# mk312_smt_main_V2b.net
KiCad netlist of a schematic drawn in EAGLE
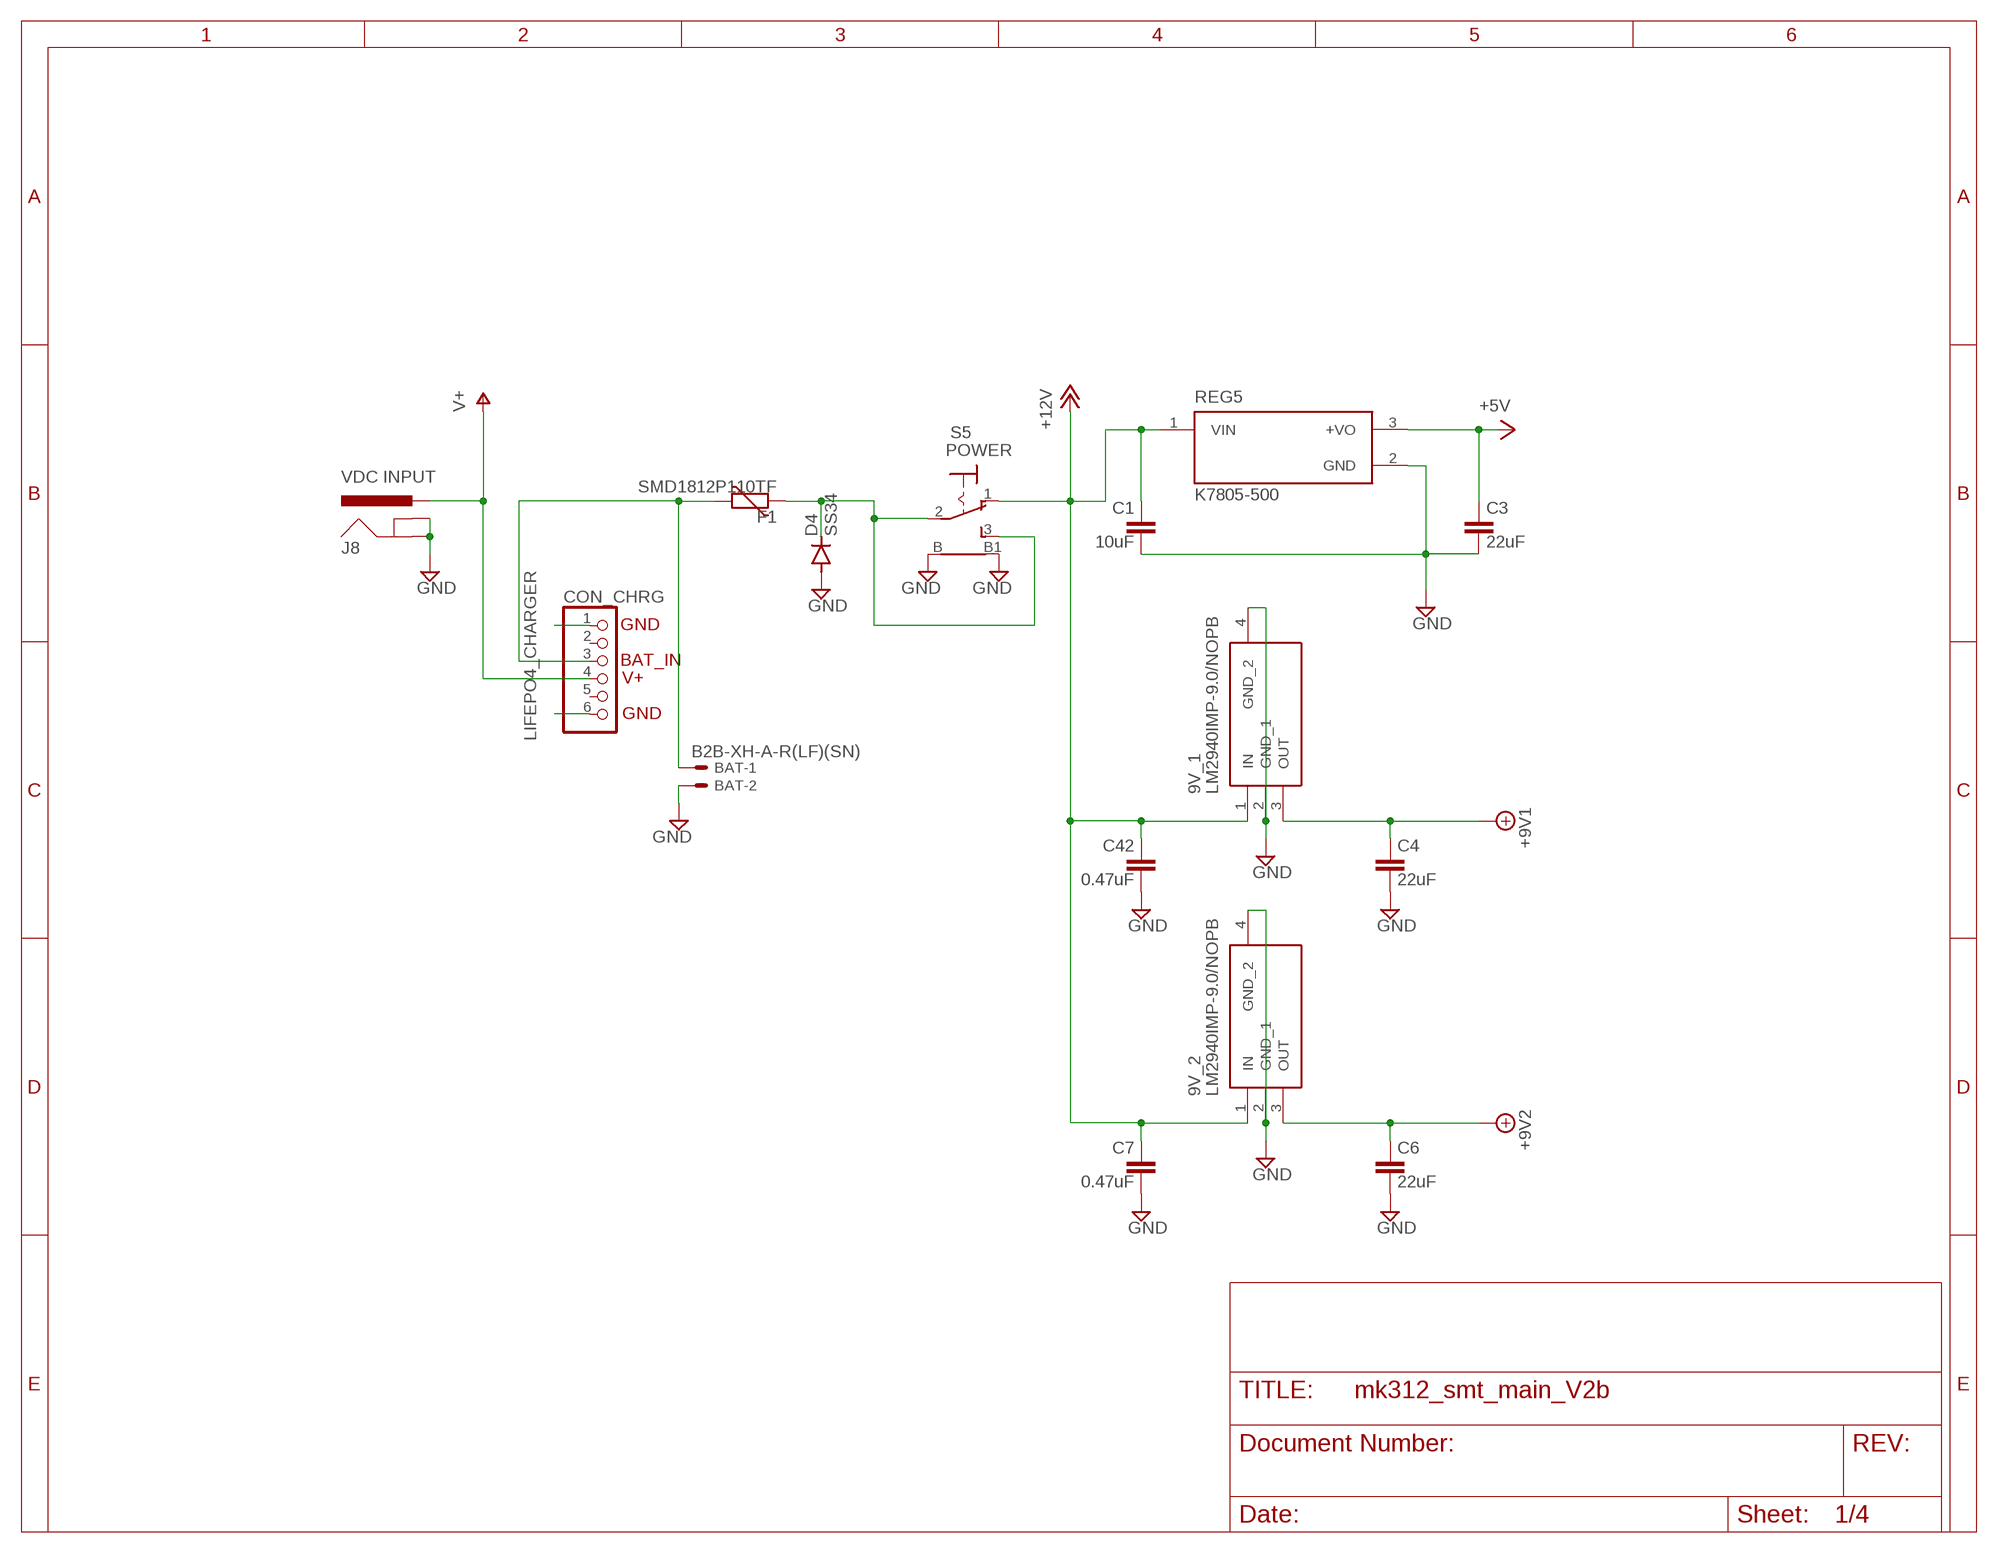
[diagram p0: schematic, sheet 1]
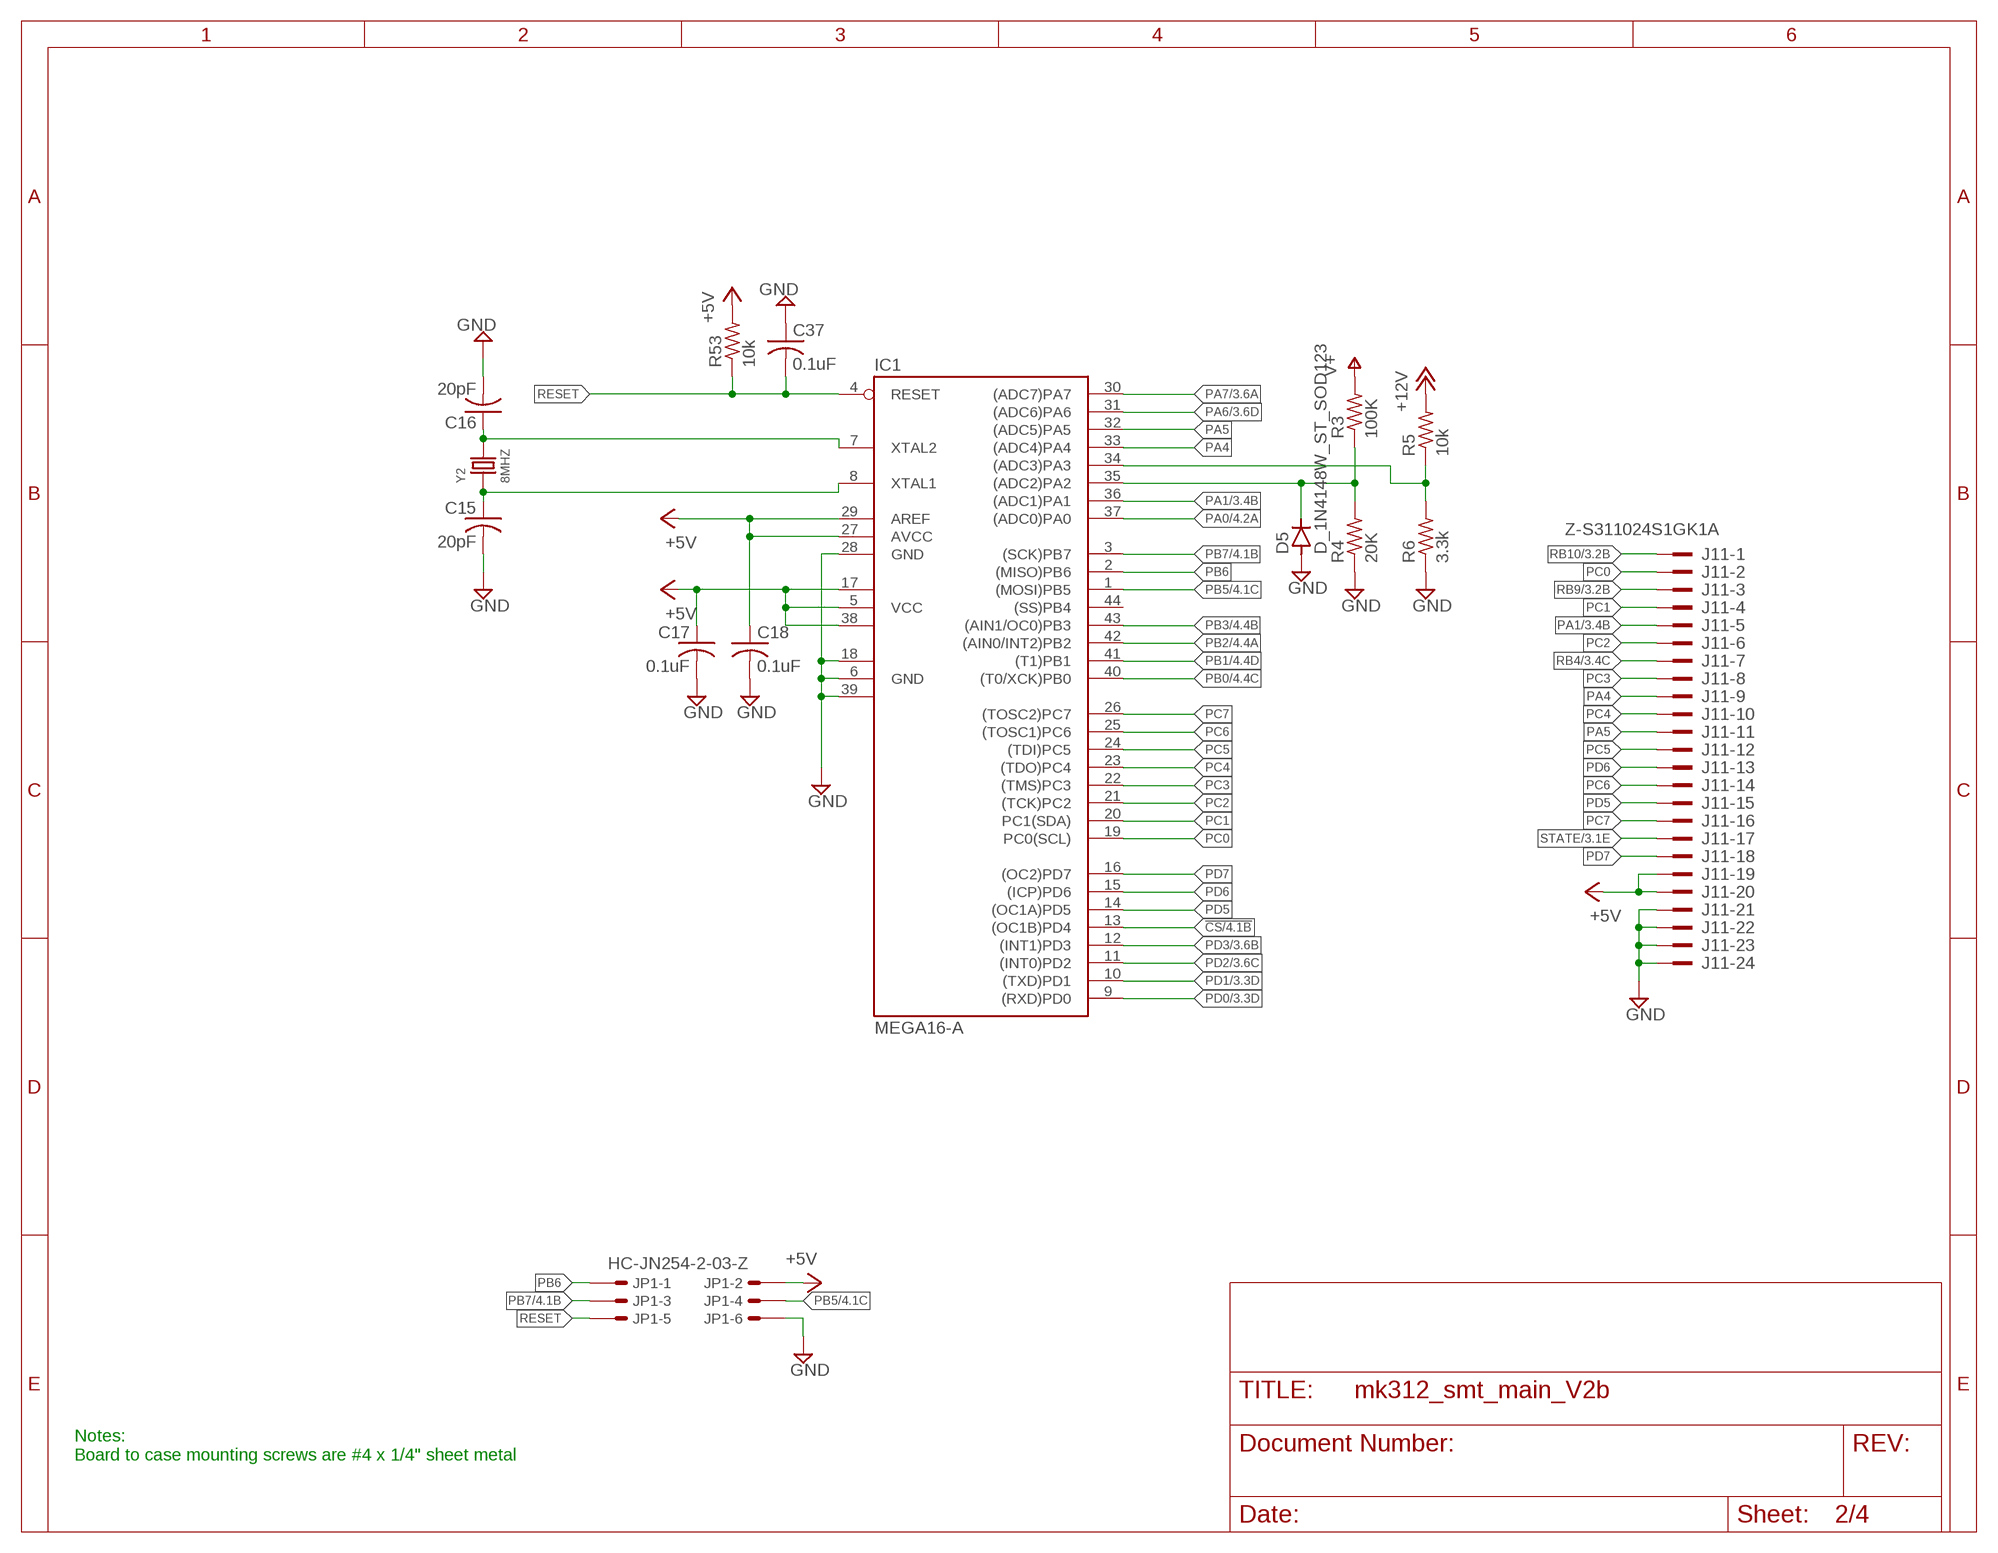
[diagram p1: schematic, sheet 2]
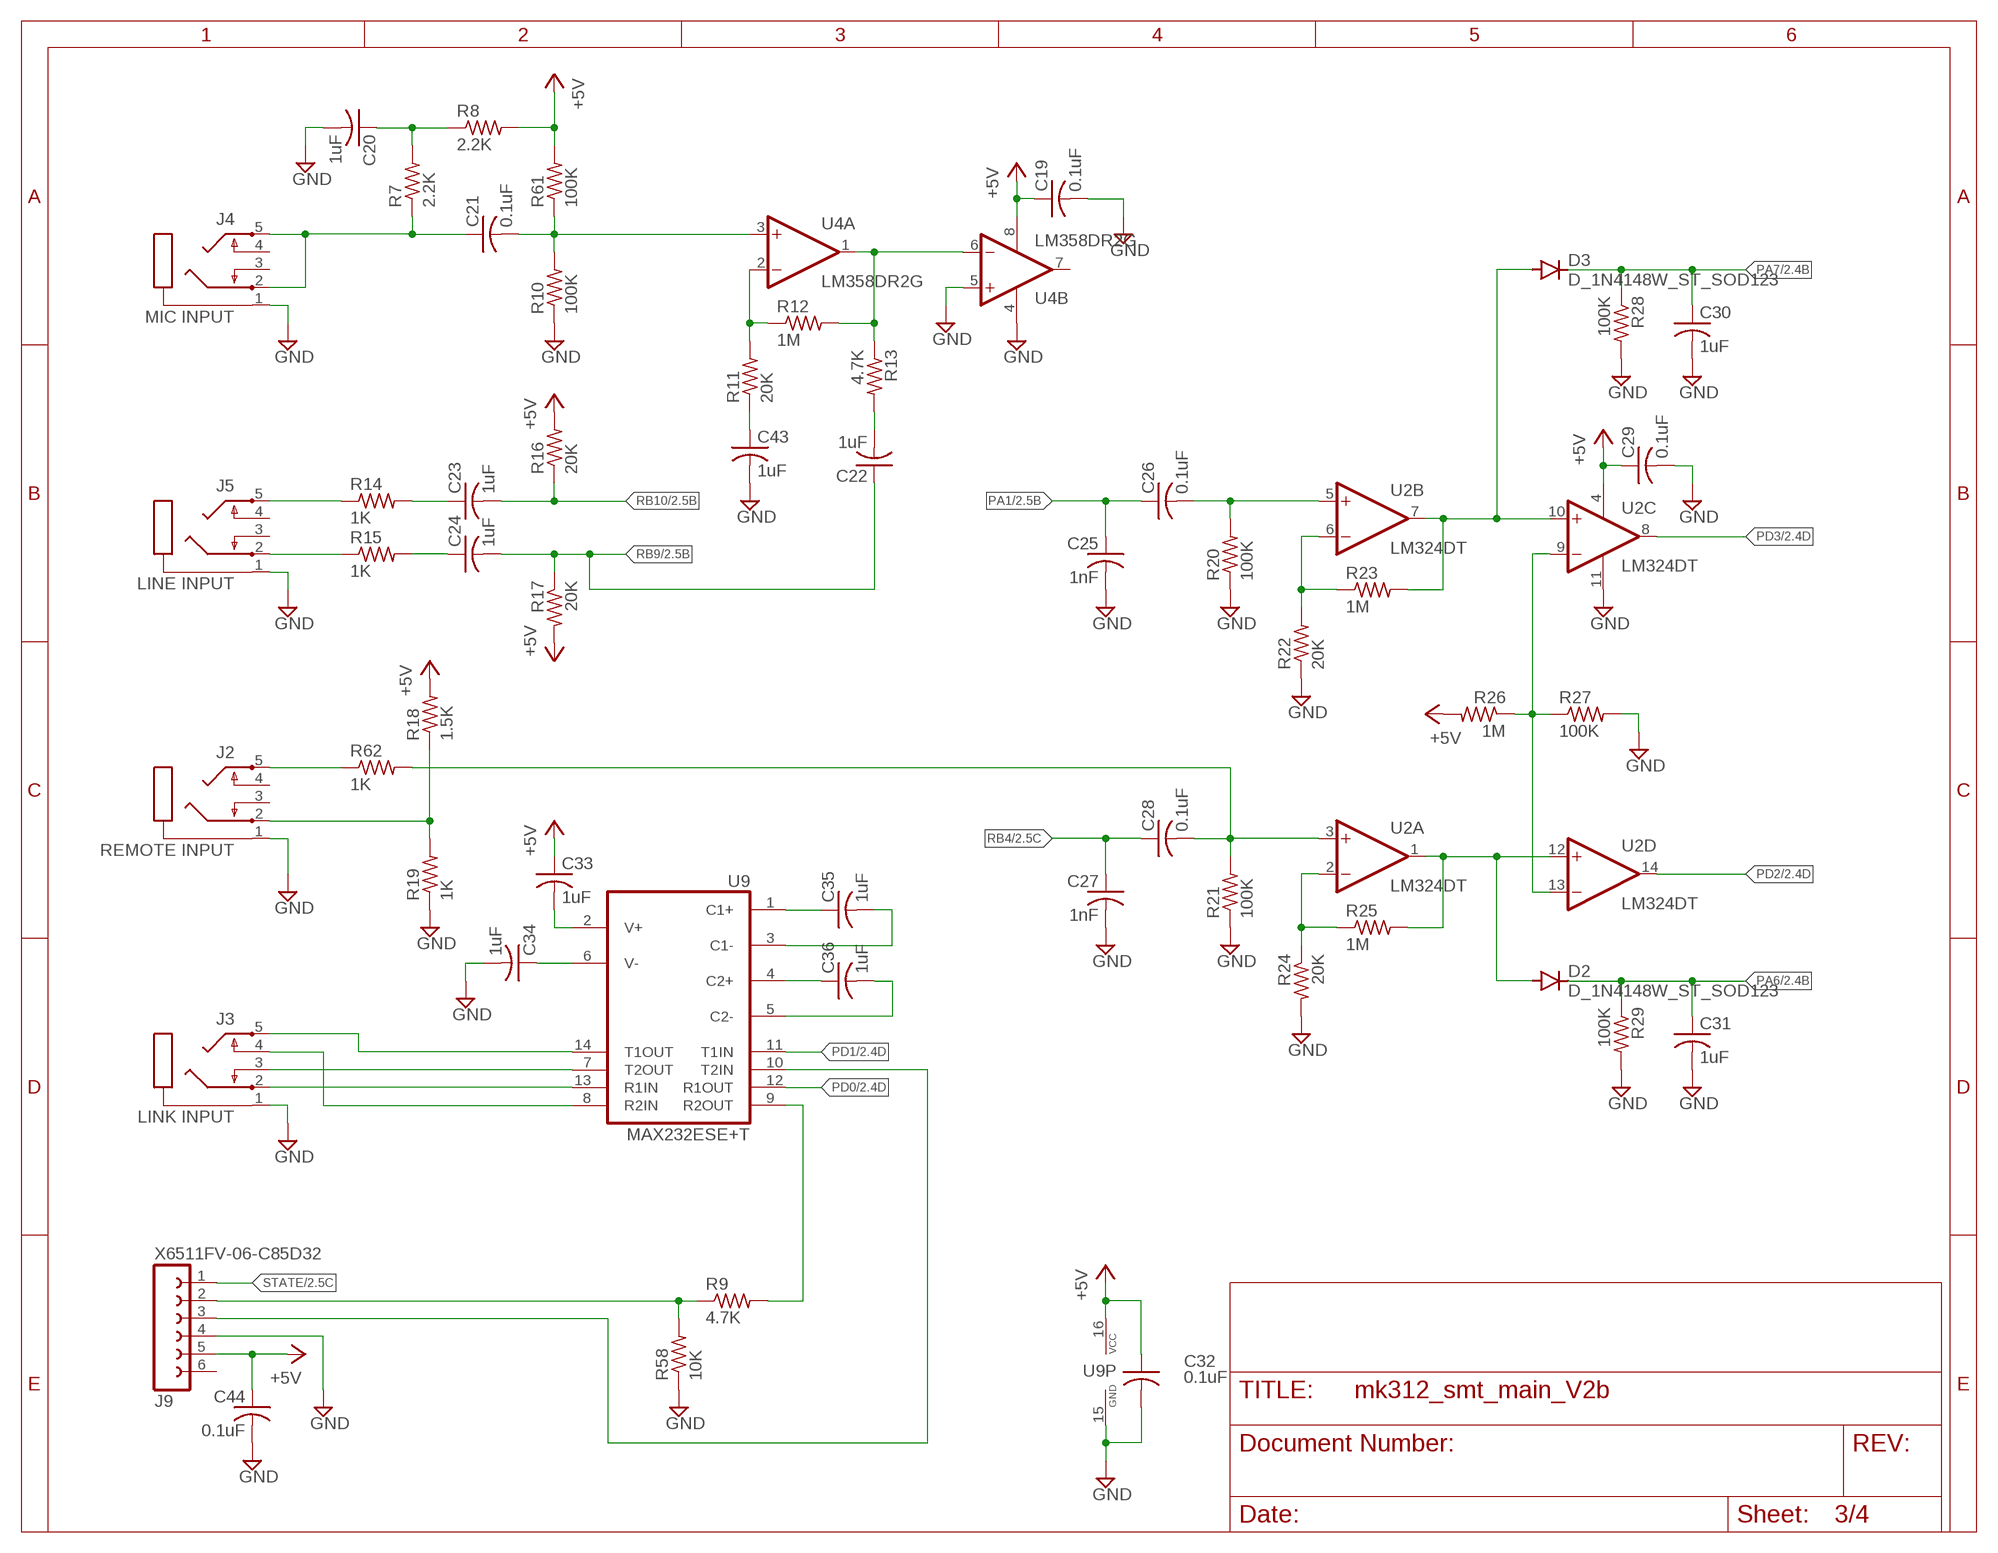
[diagram p2: schematic, sheet 3]
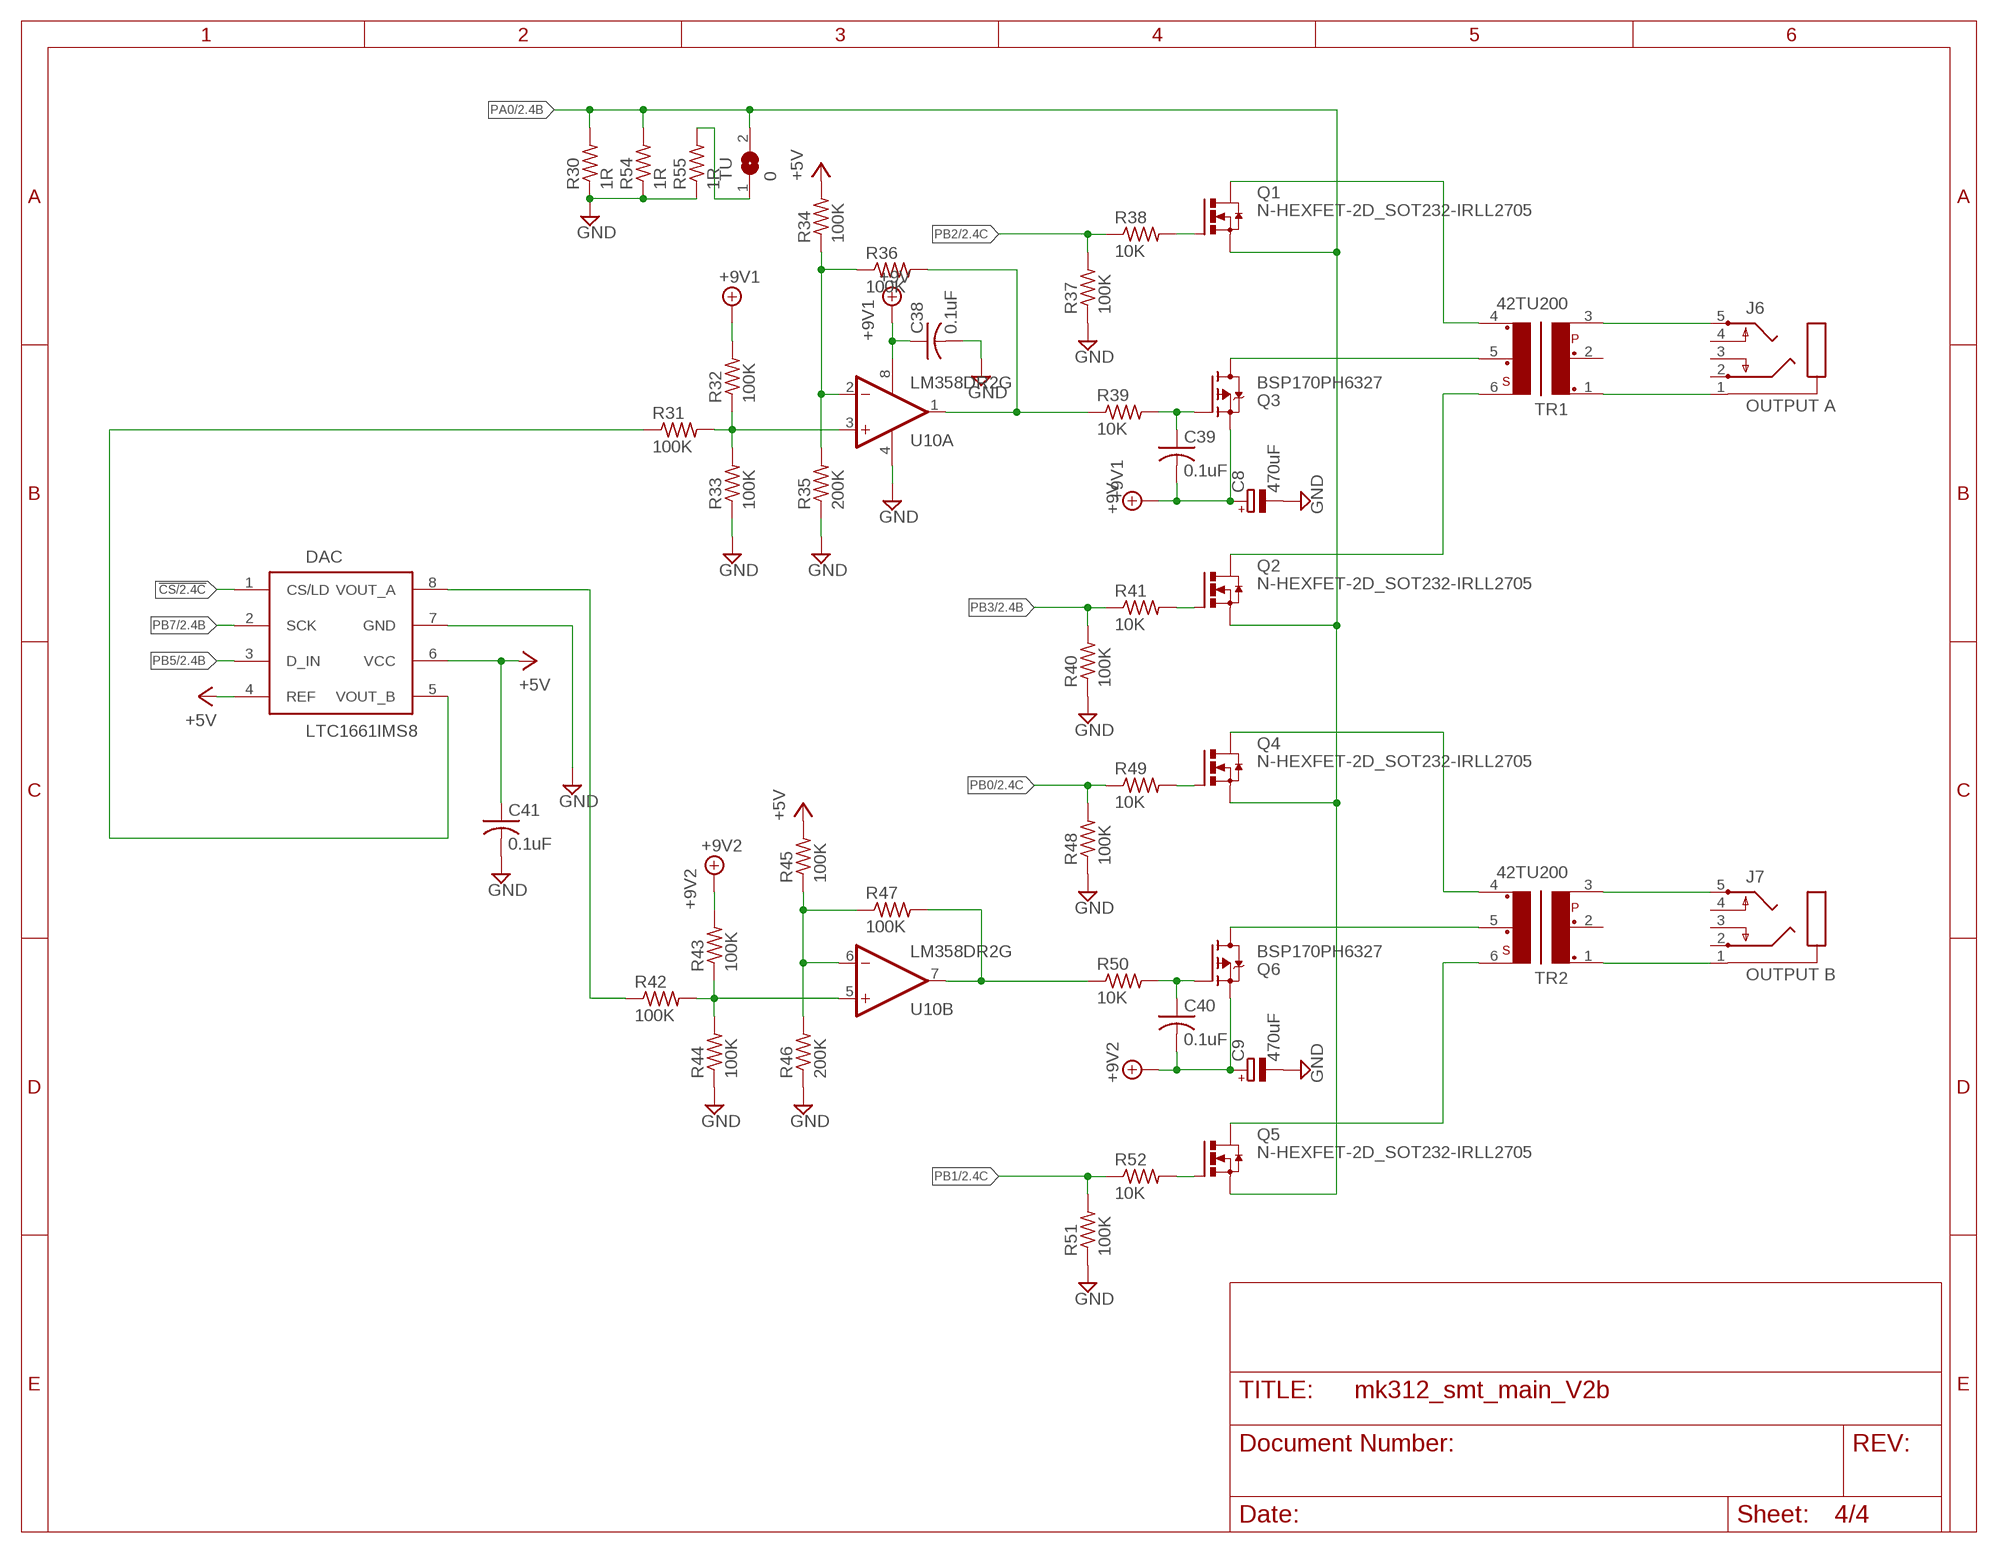
[diagram p3: schematic, sheet 4]

(export (version "E")
  (design (tool "Eeschema 10.0.6"))
  (components
    (comp (ref "9V_1")
      (value "LM2940IMP-9.0/NOPB")
      (footprint "eagle-import:SOT230P700X180-4N")
      (fields (field (name "MOUSER_PART_NUMBER") "926-LM2940IMP90NOPB"))
      (libsource (lib "eagle-import") (part "LM2940IMP-9.0_NOPB"))
    )
    (comp (ref "9V_2")
      (value "LM2940IMP-9.0/NOPB")
      (footprint "eagle-import:SOT230P700X180-4N")
      (fields (field (name "MOUSER_PART_NUMBER") "926-LM2940IMP90NOPB"))
      (libsource (lib "eagle-import") (part "LM2940IMP-9.0_NOPB"))
    )
    (comp (ref "BAT")
      (value "B2B-XH-A-R(LF)(SN)")
      (footprint "eagle-import:JST-XH-02-PACKAGE-LONG-PAD")
      (libsource (lib "eagle-import") (part "JST-XH-02-PIN-LONG-PAD"))
    )
    (comp (ref "C1")
      (value "10uF")
      (footprint "eagle-import:C0805")
      (libsource (lib "eagle-import") (part "C-EUC0805"))
    )
    (comp (ref "C3")
      (value "22uF")
      (footprint "eagle-import:C1206")
      (libsource (lib "eagle-import") (part "C-EUC1206"))
    )
    (comp (ref "C4")
      (value "22uF")
      (footprint "eagle-import:C1206")
      (libsource (lib "eagle-import") (part "C-EUC1206"))
    )
    (comp (ref "C6")
      (value "22uF")
      (footprint "eagle-import:C1206")
      (libsource (lib "eagle-import") (part "C-EUC1206"))
    )
    (comp (ref "C7")
      (value "0.47uF")
      (footprint "eagle-import:C0805")
      (libsource (lib "eagle-import") (part "C-EUC0805"))
    )
    (comp (ref "C42")
      (value "0.47uF")
      (footprint "eagle-import:C0805")
      (libsource (lib "eagle-import") (part "C-EUC0805"))
    )
    (comp (ref "CON_CHRG")
      (value "LIFEPO4_CHARGER")
      (footprint "eagle-import:LIFEPO4_CHARGER")
      (libsource (lib "eagle-import") (part "LIFEPO4_CHARGER"))
    )
    (comp (ref "D4")
      (value "SS34")
      (footprint "eagle-import:SMA")
      (libsource (lib "eagle-import") (part "S1M"))
    )
    (comp (ref "F1")
      (value "SMD1812P110TF")
      (footprint "eagle-import:CT_CN1812")
      (libsource (lib "eagle-import") (part "VARISTORCN1812"))
    )
    (comp (ref "J8")
      (value "VDC INPUT")
      (footprint "eagle-import:POWER_JACK_PTH_SLOT")
      (libsource (lib "eagle-import") (part "POWER_JACKPOWER_JACK_SLOT"))
    )
    (comp (ref "REG5")
      (value "K7805-500")
      (footprint "eagle-import:CONV_K7809M-1000R3")
      (fields (field (name "MF") "Mornsun America, LLC") (field (name "MP") "K7809M-1000R3"))
      (libsource (lib "eagle-import") (part "K7809M-1000R3"))
    )
    (comp (ref "S5")
      (value "POWER")
      (footprint "eagle-import:LPV-1")
      (libsource (lib "eagle-import") (part "LPV-1"))
    )
    (comp (ref "C8")
      (value "470uF")
      (footprint "eagle-import:150CLZ-1010")
      (libsource (lib "eagle-import") (part "CPOL-EU150CLZ-1010"))
    )
    (comp (ref "C9")
      (value "470uF")
      (footprint "eagle-import:150CLZ-1010")
      (libsource (lib "eagle-import") (part "CPOL-EU150CLZ-1010"))
    )
    (comp (ref "C38")
      (value "0.1uF")
      (footprint "eagle-import:C0805")
      (libsource (lib "eagle-import") (part "C-USC0805"))
    )
    (comp (ref "C39")
      (value "0.1uF")
      (footprint "eagle-import:C0805")
      (libsource (lib "eagle-import") (part "C-USC0805"))
    )
    (comp (ref "C40")
      (value "0.1uF")
      (footprint "eagle-import:C0805")
      (libsource (lib "eagle-import") (part "C-USC0805"))
    )
    (comp (ref "C41")
      (value "0.1uF")
      (footprint "eagle-import:C0805")
      (libsource (lib "eagle-import") (part "C-USC0805"))
    )
    (comp (ref "DAC")
      (value "LTC1661IMS8")
      (footprint "eagle-import:MSOP8")
      (libsource (lib "eagle-import") (part "LTC1661IMS8"))
    )
    (comp (ref "J6")
      (value "OUTPUT A")
      (footprint "eagle-import:PJ-3062")
      (libsource (lib "eagle-import") (part "STEREOJACKPJ-3062"))
    )
    (comp (ref "J7")
      (value "OUTPUT B")
      (footprint "eagle-import:PJ-3062")
      (libsource (lib "eagle-import") (part "STEREOJACKPJ-3062"))
    )
    (comp (ref "Q1")
      (value "N-HEXFET-2D_SOT232-IRLL2705")
      (footprint "eagle-import:SOT223")
      (libsource (lib "eagle-import") (part "N-HEXFET-2D_?-SOT232IRLL2705"))
    )
    (comp (ref "Q2")
      (value "N-HEXFET-2D_SOT232-IRLL2705")
      (footprint "eagle-import:SOT223")
      (libsource (lib "eagle-import") (part "N-HEXFET-2D_?-SOT232IRLL2705"))
    )
    (comp (ref "Q3")
      (value "BSP170PH6327")
      (footprint "eagle-import:SOT230P700X180-4N")
      (libsource (lib "eagle-import") (part "IRFL9014TRPBF"))
    )
    (comp (ref "Q4")
      (value "N-HEXFET-2D_SOT232-IRLL2705")
      (footprint "eagle-import:SOT223")
      (libsource (lib "eagle-import") (part "N-HEXFET-2D_?-SOT232IRLL2705"))
    )
    (comp (ref "Q5")
      (value "N-HEXFET-2D_SOT232-IRLL2705")
      (footprint "eagle-import:SOT223")
      (libsource (lib "eagle-import") (part "N-HEXFET-2D_?-SOT232IRLL2705"))
    )
    (comp (ref "Q6")
      (value "BSP170PH6327")
      (footprint "eagle-import:SOT230P700X180-4N")
      (libsource (lib "eagle-import") (part "IRFL9014TRPBF"))
    )
    (comp (ref "R30")
      (value "1R")
      (footprint "eagle-import:R1206")
      (libsource (lib "eagle-import") (part "R-US_R1206"))
    )
    (comp (ref "R31")
      (value "100K")
      (footprint "eagle-import:R0805")
      (libsource (lib "eagle-import") (part "R-US_R0805"))
    )
    (comp (ref "R32")
      (value "100K")
      (footprint "eagle-import:R0805")
      (libsource (lib "eagle-import") (part "R-US_R0805"))
    )
    (comp (ref "R33")
      (value "100K")
      (footprint "eagle-import:R0805")
      (libsource (lib "eagle-import") (part "R-US_R0805"))
    )
    (comp (ref "R34")
      (value "100K")
      (footprint "eagle-import:R0805")
      (libsource (lib "eagle-import") (part "R-US_R0805"))
    )
    (comp (ref "R35")
      (value "200K")
      (footprint "eagle-import:R0805")
      (libsource (lib "eagle-import") (part "R-US_R0805"))
    )
    (comp (ref "R36")
      (value "100K")
      (footprint "eagle-import:R0805")
      (libsource (lib "eagle-import") (part "R-US_R0805"))
    )
    (comp (ref "R37")
      (value "100K")
      (footprint "eagle-import:R0805")
      (libsource (lib "eagle-import") (part "R-US_R0805"))
    )
    (comp (ref "R38")
      (value "10K")
      (footprint "eagle-import:R0805")
      (libsource (lib "eagle-import") (part "R-US_R0805"))
    )
    (comp (ref "R39")
      (value "10K")
      (footprint "eagle-import:R0805")
      (libsource (lib "eagle-import") (part "R-US_R0805"))
    )
    (comp (ref "R40")
      (value "100K")
      (footprint "eagle-import:R0805")
      (libsource (lib "eagle-import") (part "R-US_R0805"))
    )
    (comp (ref "R41")
      (value "10K")
      (footprint "eagle-import:R0805")
      (libsource (lib "eagle-import") (part "R-US_R0805"))
    )
    (comp (ref "R42")
      (value "100K")
      (footprint "eagle-import:R0805")
      (libsource (lib "eagle-import") (part "R-US_R0805"))
    )
    (comp (ref "R43")
      (value "100K")
      (footprint "eagle-import:R0805")
      (libsource (lib "eagle-import") (part "R-US_R0805"))
    )
    (comp (ref "R44")
      (value "100K")
      (footprint "eagle-import:R0805")
      (libsource (lib "eagle-import") (part "R-US_R0805"))
    )
    (comp (ref "R45")
      (value "100K")
      (footprint "eagle-import:R0805")
      (libsource (lib "eagle-import") (part "R-US_R0805"))
    )
    (comp (ref "R46")
      (value "200K")
      (footprint "eagle-import:R0805")
      (libsource (lib "eagle-import") (part "R-US_R0805"))
    )
    (comp (ref "R47")
      (value "100K")
      (footprint "eagle-import:R0805")
      (libsource (lib "eagle-import") (part "R-US_R0805"))
    )
    (comp (ref "R48")
      (value "100K")
      (footprint "eagle-import:R0805")
      (libsource (lib "eagle-import") (part "R-US_R0805"))
    )
    (comp (ref "R49")
      (value "10K")
      (footprint "eagle-import:R0805")
      (libsource (lib "eagle-import") (part "R-US_R0805"))
    )
    (comp (ref "R50")
      (value "10K")
      (footprint "eagle-import:R0805")
      (libsource (lib "eagle-import") (part "R-US_R0805"))
    )
    (comp (ref "R51")
      (value "100K")
      (footprint "eagle-import:R0805")
      (libsource (lib "eagle-import") (part "R-US_R0805"))
    )
    (comp (ref "R52")
      (value "10K")
      (footprint "eagle-import:R0805")
      (libsource (lib "eagle-import") (part "R-US_R0805"))
    )
    (comp (ref "R54")
      (value "1R")
      (footprint "eagle-import:R1206")
      (libsource (lib "eagle-import") (part "R-US_R1206"))
    )
    (comp (ref "R55")
      (value "1R")
      (footprint "eagle-import:R1206")
      (libsource (lib "eagle-import") (part "R-US_R1206"))
    )
    (comp (ref "TR1")
      (value "42TU200")
      (footprint "eagle-import:42TL")
      (libsource (lib "eagle-import") (part "42T?42TU"))
    )
    (comp (ref "TR2")
      (value "42TU200")
      (footprint "eagle-import:42TL")
      (libsource (lib "eagle-import") (part "42T?42TU"))
    )
    (comp (ref "TU") (value "0") (footprint "eagle-import:SJ") (libsource (lib "eagle-import") (part "SJ")))
    (comp (ref "U10")
      (value "LM358DR2G")
      (footprint "eagle-import:SO08")
      (libsource (lib "eagle-import") (part "LM358D"))
    )
    (comp (ref "C15")
      (value "20pF")
      (footprint "eagle-import:C0603")
      (libsource (lib "eagle-import") (part "C-USC0603"))
    )
    (comp (ref "C16")
      (value "20pF")
      (footprint "eagle-import:C0603")
      (libsource (lib "eagle-import") (part "C-USC0603"))
    )
    (comp (ref "C17")
      (value "0.1uF")
      (footprint "eagle-import:C0805")
      (libsource (lib "eagle-import") (part "C-USC0805"))
    )
    (comp (ref "C18")
      (value "0.1uF")
      (footprint "eagle-import:C0805")
      (libsource (lib "eagle-import") (part "C-USC0805"))
    )
    (comp (ref "C37")
      (value "0.1uF")
      (footprint "eagle-import:C0805")
      (libsource (lib "eagle-import") (part "rcl_334_C-USC0805"))
    )
    (comp (ref "D5")
      (value "D_1N4148W_ST_SOD123")
      (footprint "eagle-import:SOD123")
      (fields (field (name "LCSC_PART") "C81598"))
      (libsource (lib "eagle-import") (part "D__SOD1231N4148W_ST"))
    )
    (comp (ref "IC1")
      (value "MEGA16-A")
      (footprint "eagle-import:TQFP44")
      (fields (field (name "MPN") "ATMEGA16-16AU"))
      (libsource (lib "eagle-import") (part "MEGA16-A"))
    )
    (comp (ref "J11")
      (value "Z-S311024S1GK1A")
      (footprint "eagle-import:PAK100_2500-24")
      (libsource (lib "eagle-import") (part "2524-"))
    )
    (comp (ref "JP1")
      (value "HC-JN254-2-03-Z")
      (footprint "eagle-import:057-006-1")
      (libsource (lib "eagle-import") (part "057-006-1"))
    )
    (comp (ref "R3")
      (value "100K")
      (footprint "eagle-import:R0805")
      (libsource (lib "eagle-import") (part "R-US_R0805"))
    )
    (comp (ref "R4")
      (value "20K")
      (footprint "eagle-import:R0805")
      (libsource (lib "eagle-import") (part "R-US_R0805"))
    )
    (comp (ref "R5")
      (value "10k")
      (footprint "eagle-import:R0805")
      (libsource (lib "eagle-import") (part "R-US_R0805"))
    )
    (comp (ref "R6")
      (value "3.3k")
      (footprint "eagle-import:R0805")
      (libsource (lib "eagle-import") (part "R-US_R0805"))
    )
    (comp (ref "R53")
      (value "10k")
      (footprint "eagle-import:R0805")
      (libsource (lib "eagle-import") (part "rcl_334_R-US_R0805"))
    )
    (comp (ref "Y2")
      (value "8MHZ")
      (footprint "eagle-import:X2-SMD-5.0X3.2X1.3MM")
      (fields (field (name "MPN") "5032/2P"))
      (libsource (lib "eagle-import") (part "SMD-CRYSTAL-8MHZ-20PF-20PPM(2P-5.0X3.2MM)"))
    )
    (comp (ref "C19")
      (value "0.1uF")
      (footprint "eagle-import:C0805")
      (libsource (lib "eagle-import") (part "C-USC0805"))
    )
    (comp (ref "C20")
      (value "1uF")
      (footprint "eagle-import:C0805")
      (libsource (lib "eagle-import") (part "C-USC0805"))
    )
    (comp (ref "C21")
      (value "0.1uF")
      (footprint "eagle-import:C0805")
      (libsource (lib "eagle-import") (part "C-USC0805"))
    )
    (comp (ref "C22")
      (value "1uF")
      (footprint "eagle-import:C0805")
      (libsource (lib "eagle-import") (part "C-USC0805"))
    )
    (comp (ref "C23")
      (value "1uF")
      (footprint "eagle-import:C0805")
      (libsource (lib "eagle-import") (part "C-USC0805"))
    )
    (comp (ref "C24")
      (value "1uF")
      (footprint "eagle-import:C0805")
      (libsource (lib "eagle-import") (part "C-USC0805"))
    )
    (comp (ref "C25")
      (value "1nF")
      (footprint "eagle-import:C0805")
      (libsource (lib "eagle-import") (part "C-USC0805"))
    )
    (comp (ref "C26")
      (value "0.1uF")
      (footprint "eagle-import:C0805")
      (libsource (lib "eagle-import") (part "C-USC0805"))
    )
    (comp (ref "C27")
      (value "1nF")
      (footprint "eagle-import:C0805")
      (libsource (lib "eagle-import") (part "C-USC0805"))
    )
    (comp (ref "C28")
      (value "0.1uF")
      (footprint "eagle-import:C0805")
      (libsource (lib "eagle-import") (part "C-USC0805"))
    )
    (comp (ref "C29")
      (value "0.1uF")
      (footprint "eagle-import:C0805")
      (libsource (lib "eagle-import") (part "C-USC0805"))
    )
    (comp (ref "C30")
      (value "1uF")
      (footprint "eagle-import:C0805")
      (libsource (lib "eagle-import") (part "C-USC0805"))
    )
    (comp (ref "C31")
      (value "1uF")
      (footprint "eagle-import:C0805")
      (libsource (lib "eagle-import") (part "C-USC0805"))
    )
    (comp (ref "C32")
      (value "0.1uF")
      (footprint "eagle-import:C0805")
      (libsource (lib "eagle-import") (part "C-USC0805"))
    )
    (comp (ref "C33")
      (value "1uF")
      (footprint "eagle-import:C0805")
      (libsource (lib "eagle-import") (part "C-USC0805"))
    )
    (comp (ref "C34")
      (value "1uF")
      (footprint "eagle-import:C0805")
      (libsource (lib "eagle-import") (part "C-USC0805"))
    )
    (comp (ref "C35")
      (value "1uF")
      (footprint "eagle-import:C0805")
      (libsource (lib "eagle-import") (part "C-USC0805"))
    )
    (comp (ref "C36")
      (value "1uF")
      (footprint "eagle-import:C0805")
      (libsource (lib "eagle-import") (part "C-USC0805"))
    )
    (comp (ref "C43")
      (value "1uF")
      (footprint "eagle-import:C0805")
      (libsource (lib "eagle-import") (part "C-USC0805"))
    )
    (comp (ref "C44")
      (value "0.1uF")
      (footprint "eagle-import:C0805")
      (libsource (lib "eagle-import") (part "C-USC0805"))
    )
    (comp (ref "D2")
      (value "D_1N4148W_ST_SOD123")
      (footprint "eagle-import:SOD123")
      (fields (field (name "LCSC_PART") "C81598"))
      (libsource (lib "eagle-import") (part "D__SOD1231N4148W_ST"))
    )
    (comp (ref "D3")
      (value "D_1N4148W_ST_SOD123")
      (footprint "eagle-import:SOD123")
      (fields (field (name "LCSC_PART") "C81598"))
      (libsource (lib "eagle-import") (part "D__SOD1231N4148W_ST"))
    )
    (comp (ref "J2")
      (value "REMOTE INPUT")
      (footprint "eagle-import:PJ-3062")
      (libsource (lib "eagle-import") (part "STEREOJACKPJ-3062"))
    )
    (comp (ref "J3")
      (value "LINK INPUT")
      (footprint "eagle-import:PJ-3062")
      (libsource (lib "eagle-import") (part "STEREOJACKPJ-3062"))
    )
    (comp (ref "J4")
      (value "MIC INPUT")
      (footprint "eagle-import:PJ-3062")
      (libsource (lib "eagle-import") (part "STEREOJACKPJ-3062"))
    )
    (comp (ref "J5")
      (value "LINE INPUT")
      (footprint "eagle-import:PJ-3062")
      (libsource (lib "eagle-import") (part "STEREOJACKPJ-3062"))
    )
    (comp (ref "J9")
      (value "X6511FV-06-C85D32")
      (footprint "eagle-import:FE06")
      (libsource (lib "eagle-import") (part "FE06-1"))
    )
    (comp (ref "R7")
      (value "2.2K")
      (footprint "eagle-import:R0805")
      (libsource (lib "eagle-import") (part "R-US_R0805"))
    )
    (comp (ref "R8")
      (value "2.2K")
      (footprint "eagle-import:R0805")
      (libsource (lib "eagle-import") (part "R-US_R0805"))
    )
    (comp (ref "R9")
      (value "4.7K")
      (footprint "eagle-import:R0805")
      (libsource (lib "eagle-import") (part "R-US_R0805"))
    )
    (comp (ref "R10")
      (value "100K")
      (footprint "eagle-import:R0805")
      (libsource (lib "eagle-import") (part "R-US_R0805"))
    )
    (comp (ref "R11")
      (value "20K")
      (footprint "eagle-import:R0805")
      (libsource (lib "eagle-import") (part "R-US_R0805"))
    )
    (comp (ref "R12")
      (value "1M")
      (footprint "eagle-import:R0805")
      (libsource (lib "eagle-import") (part "R-US_R0805"))
    )
    (comp (ref "R13")
      (value "4.7K")
      (footprint "eagle-import:R0805")
      (libsource (lib "eagle-import") (part "R-US_R0805"))
    )
    (comp (ref "R14")
      (value "1K")
      (footprint "eagle-import:R0805")
      (libsource (lib "eagle-import") (part "R-US_R0805"))
    )
    (comp (ref "R15")
      (value "1K")
      (footprint "eagle-import:R0805")
      (libsource (lib "eagle-import") (part "R-US_R0805"))
    )
    (comp (ref "R16")
      (value "20K")
      (footprint "eagle-import:R0805")
      (libsource (lib "eagle-import") (part "R-US_R0805"))
    )
    (comp (ref "R17")
      (value "20K")
      (footprint "eagle-import:R0805")
      (libsource (lib "eagle-import") (part "R-US_R0805"))
    )
    (comp (ref "R18")
      (value "1.5K")
      (footprint "eagle-import:R0805")
      (libsource (lib "eagle-import") (part "R-US_R0805"))
    )
    (comp (ref "R19")
      (value "1K")
      (footprint "eagle-import:R0805")
      (libsource (lib "eagle-import") (part "R-US_R0805"))
    )
    (comp (ref "R20")
      (value "100K")
      (footprint "eagle-import:R0805")
      (libsource (lib "eagle-import") (part "R-US_R0805"))
    )
    (comp (ref "R21")
      (value "100K")
      (footprint "eagle-import:R0805")
      (libsource (lib "eagle-import") (part "R-US_R0805"))
    )
    (comp (ref "R22")
      (value "20K")
      (footprint "eagle-import:R0805")
      (libsource (lib "eagle-import") (part "R-US_R0805"))
    )
    (comp (ref "R23")
      (value "1M")
      (footprint "eagle-import:R0805")
      (libsource (lib "eagle-import") (part "R-US_R0805"))
    )
    (comp (ref "R24")
      (value "20K")
      (footprint "eagle-import:R0805")
      (libsource (lib "eagle-import") (part "R-US_R0805"))
    )
    (comp (ref "R25")
      (value "1M")
      (footprint "eagle-import:R0805")
      (libsource (lib "eagle-import") (part "R-US_R0805"))
    )
    (comp (ref "R26")
      (value "1M")
      (footprint "eagle-import:R0805")
      (libsource (lib "eagle-import") (part "R-US_R0805"))
    )
    (comp (ref "R27")
      (value "100K")
      (footprint "eagle-import:R0805")
      (libsource (lib "eagle-import") (part "R-US_R0805"))
    )
    (comp (ref "R28")
      (value "100K")
      (footprint "eagle-import:R0805")
      (libsource (lib "eagle-import") (part "R-US_R0805"))
    )
    (comp (ref "R29")
      (value "100K")
      (footprint "eagle-import:R0805")
      (libsource (lib "eagle-import") (part "R-US_R0805"))
    )
    (comp (ref "R58")
      (value "10K")
      (footprint "eagle-import:R0805")
      (libsource (lib "eagle-import") (part "R-US_R0805"))
    )
    (comp (ref "R61")
      (value "100K")
      (footprint "eagle-import:R0805")
      (libsource (lib "eagle-import") (part "R-US_R0805"))
    )
    (comp (ref "R62")
      (value "1K")
      (footprint "eagle-import:R0805")
      (libsource (lib "eagle-import") (part "R-US_R0805"))
    )
    (comp (ref "U2")
      (value "LM324DT")
      (footprint "eagle-import:SO14")
      (libsource (lib "eagle-import") (part "LM324D"))
    )
    (comp (ref "U4")
      (value "LM358DR2G")
      (footprint "eagle-import:SO08")
      (libsource (lib "eagle-import") (part "LM358D"))
    )
    (comp (ref "U9")
      (value "MAX232ESE+T")
      (footprint "eagle-import:SOP-16")
      (libsource (lib "eagle-import") (part "MAX232ECWESOP16"))
    )
  )
  (nets
    (net (code "1") (name "+5V") (class "Default")
      (node (ref "C17") (pin "1") (pinfunction "1_1") (pintype "passive"))
      (node (ref "C18") (pin "1") (pinfunction "1_1") (pintype "passive"))
      (node (ref "C19") (pin "1") (pinfunction "1_1") (pintype "passive"))
      (node (ref "C29") (pin "1") (pinfunction "1_1") (pintype "passive"))
      (node (ref "C3") (pin "1") (pinfunction "1_1") (pintype "passive"))
      (node (ref "C32") (pin "1") (pinfunction "1_1") (pintype "passive"))
      (node (ref "C33") (pin "1") (pinfunction "1_1") (pintype "passive"))
      (node (ref "C41") (pin "1") (pinfunction "1_1") (pintype "passive"))
      (node (ref "C44") (pin "1") (pinfunction "1_1") (pintype "passive"))
      (node (ref "DAC") (pin "4") (pinfunction "REF_4") (pintype "input"))
      (node (ref "DAC") (pin "6") (pinfunction "VCC_6") (pintype "power_in"))
      (node (ref "IC1") (pin "17") (pinfunction "VCC1_17") (pintype "power_in"))
      (node (ref "IC1") (pin "27") (pinfunction "AVCC_27") (pintype "power_in"))
      (node (ref "IC1") (pin "29") (pinfunction "AREF_29") (pintype "passive"))
      (node (ref "IC1") (pin "38") (pinfunction "VCC2_38") (pintype "power_in"))
      (node (ref "IC1") (pin "5") (pinfunction "VCC_5") (pintype "power_in"))
      (node (ref "J11") (pin "19") (pinfunction "KL_19") (pintype "passive"))
      (node (ref "J11") (pin "20") (pinfunction "KL_20") (pintype "passive"))
      (node (ref "J9") (pin "5") (pinfunction "5_5") (pintype "passive"))
      (node (ref "JP1") (pin "2") (pinfunction "S_2") (pintype "passive"))
      (node (ref "R16") (pin "2") (pinfunction "2_2") (pintype "passive"))
      (node (ref "R17") (pin "2") (pinfunction "2_2") (pintype "passive"))
      (node (ref "R18") (pin "2") (pinfunction "2_2") (pintype "passive"))
      (node (ref "R26") (pin "2") (pinfunction "2_2") (pintype "passive"))
      (node (ref "R34") (pin "2") (pinfunction "2_2") (pintype "passive"))
      (node (ref "R45") (pin "2") (pinfunction "2_2") (pintype "passive"))
      (node (ref "R53") (pin "2") (pinfunction "2_2") (pintype "passive"))
      (node (ref "R61") (pin "2") (pinfunction "2_2") (pintype "passive"))
      (node (ref "R8") (pin "2") (pinfunction "2_2") (pintype "passive"))
      (node (ref "REG5") (pin "3") (pinfunction "+VO_3") (pintype "output"))
      (node (ref "U2") (pin "4") (pinfunction "V+_4") (pintype "power_in"))
      (node (ref "U4") (pin "8") (pinfunction "V+_8") (pintype "power_in"))
      (node (ref "U9") (pin "16") (pinfunction "VCC_16") (pintype "power_in"))
    )
    (net (code "2") (name "+9V1") (class "Default")
      (node (ref "9V_1") (pin "3") (pinfunction "OUT_3") (pintype "power_in"))
      (node (ref "C38") (pin "1") (pinfunction "1_1") (pintype "passive"))
      (node (ref "C39") (pin "2") (pinfunction "2_2") (pintype "passive"))
      (node (ref "C4") (pin "1") (pinfunction "1_1") (pintype "passive"))
      (node (ref "C8") (pin "+") (pinfunction "+_+") (pintype "passive"))
      (node (ref "Q3") (pin "3") (pinfunction "S_3") (pintype "passive"))
      (node (ref "R32") (pin "2") (pinfunction "2_2") (pintype "passive"))
      (node (ref "U10") (pin "8") (pinfunction "V+_8") (pintype "power_in"))
    )
    (net (code "3") (name "+9V2") (class "Default")
      (node (ref "9V_2") (pin "3") (pinfunction "OUT_3") (pintype "power_in"))
      (node (ref "C40") (pin "2") (pinfunction "2_2") (pintype "passive"))
      (node (ref "C6") (pin "1") (pinfunction "1_1") (pintype "passive"))
      (node (ref "C9") (pin "+") (pinfunction "+_+") (pintype "passive"))
      (node (ref "Q6") (pin "3") (pinfunction "S_3") (pintype "passive"))
      (node (ref "R43") (pin "2") (pinfunction "2_2") (pintype "passive"))
    )
    (net (code "4") (name "+12V") (class "Default")
      (node (ref "9V_1") (pin "1") (pinfunction "IN_1") (pintype "input"))
      (node (ref "9V_2") (pin "1") (pinfunction "IN_1") (pintype "input"))
      (node (ref "C1") (pin "1") (pinfunction "1_1") (pintype "passive"))
      (node (ref "C42") (pin "1") (pinfunction "1_1") (pintype "passive"))
      (node (ref "C7") (pin "1") (pinfunction "1_1") (pintype "passive"))
      (node (ref "R5") (pin "2") (pinfunction "2_2") (pintype "passive"))
      (node (ref "REG5") (pin "1") (pinfunction "VIN_1") (pintype "input"))
      (node (ref "S5") (pin "1") (pinfunction "O_1") (pintype "passive"))
    )
    (net (code "5") (name "GND") (class "Default")
      (node (ref "9V_1") (pin "2") (pinfunction "GND_1_2") (pintype "power_in"))
      (node (ref "9V_1") (pin "4") (pinfunction "GND_2_4") (pintype "power_in"))
      (node (ref "9V_2") (pin "2") (pinfunction "GND_1_2") (pintype "power_in"))
      (node (ref "9V_2") (pin "4") (pinfunction "GND_2_4") (pintype "power_in"))
      (node (ref "BAT") (pin "2") (pinfunction "S_2") (pintype "passive"))
      (node (ref "C1") (pin "2") (pinfunction "2_2") (pintype "passive"))
      (node (ref "C15") (pin "2") (pinfunction "2_2") (pintype "passive"))
      (node (ref "C16") (pin "2") (pinfunction "2_2") (pintype "passive"))
      (node (ref "C17") (pin "2") (pinfunction "2_2") (pintype "passive"))
      (node (ref "C18") (pin "2") (pinfunction "2_2") (pintype "passive"))
      (node (ref "C19") (pin "2") (pinfunction "2_2") (pintype "passive"))
      (node (ref "C20") (pin "2") (pinfunction "2_2") (pintype "passive"))
      (node (ref "C25") (pin "2") (pinfunction "2_2") (pintype "passive"))
      (node (ref "C27") (pin "2") (pinfunction "2_2") (pintype "passive"))
      (node (ref "C29") (pin "2") (pinfunction "2_2") (pintype "passive"))
      (node (ref "C3") (pin "2") (pinfunction "2_2") (pintype "passive"))
      (node (ref "C30") (pin "2") (pinfunction "2_2") (pintype "passive"))
      (node (ref "C31") (pin "2") (pinfunction "2_2") (pintype "passive"))
      (node (ref "C32") (pin "2") (pinfunction "2_2") (pintype "passive"))
      (node (ref "C34") (pin "2") (pinfunction "2_2") (pintype "passive"))
      (node (ref "C37") (pin "1") (pinfunction "1_1") (pintype "passive"))
      (node (ref "C38") (pin "2") (pinfunction "2_2") (pintype "passive"))
      (node (ref "C4") (pin "2") (pinfunction "2_2") (pintype "passive"))
      (node (ref "C41") (pin "2") (pinfunction "2_2") (pintype "passive"))
      (node (ref "C42") (pin "2") (pinfunction "2_2") (pintype "passive"))
      (node (ref "C43") (pin "2") (pinfunction "2_2") (pintype "passive"))
      (node (ref "C44") (pin "2") (pinfunction "2_2") (pintype "passive"))
      (node (ref "C6") (pin "2") (pinfunction "2_2") (pintype "passive"))
      (node (ref "C7") (pin "2") (pinfunction "2_2") (pintype "passive"))
      (node (ref "C8") (pin "-") (pinfunction "-_-") (pintype "passive"))
      (node (ref "C9") (pin "-") (pinfunction "-_-") (pintype "passive"))
      (node (ref "CON_CHRG") (pin "1") (pinfunction "GND_1_1") (pintype "power_in"))
      (node (ref "CON_CHRG") (pin "6") (pinfunction "GND_2_6") (pintype "power_in"))
      (node (ref "D4") (pin "A") (pinfunction "A_A") (pintype "passive"))
      (node (ref "D5") (pin "A") (pinfunction "A_A") (pintype "passive"))
      (node (ref "DAC") (pin "7") (pinfunction "GND_7") (pintype "power_in"))
      (node (ref "IC1") (pin "18") (pinfunction "GND1_18") (pintype "power_in"))
      (node (ref "IC1") (pin "28") (pinfunction "GND_28") (pintype "power_in"))
      (node (ref "IC1") (pin "39") (pinfunction "GND2_39") (pintype "power_in"))
      (node (ref "IC1") (pin "6") (pinfunction "GND_6") (pintype "power_in"))
      (node (ref "J11") (pin "21") (pinfunction "KL_21") (pintype "passive"))
      (node (ref "J11") (pin "22") (pinfunction "KL_22") (pintype "passive"))
      (node (ref "J11") (pin "23") (pinfunction "KL_23") (pintype "passive"))
      (node (ref "J11") (pin "24") (pinfunction "KL_24") (pintype "passive"))
      (node (ref "J2") (pin "1") (pinfunction "1_1") (pintype "passive"))
      (node (ref "J3") (pin "1") (pinfunction "1_1") (pintype "passive"))
      (node (ref "J4") (pin "1") (pinfunction "1_1") (pintype "passive"))
      (node (ref "J5") (pin "1") (pinfunction "1_1") (pintype "passive"))
      (node (ref "J8") (pin "GND") (pinfunction "GND_GND") (pintype "bidirectional"))
      (node (ref "J8") (pin "GNDBREAK") (pinfunction "GNDBREAK_GNDBREAK") (pintype "bidirectional"))
      (node (ref "J9") (pin "4") (pinfunction "4_4") (pintype "passive"))
      (node (ref "JP1") (pin "6") (pinfunction "S_6") (pintype "passive"))
      (node (ref "R10") (pin "1") (pinfunction "1_1") (pintype "passive"))
      (node (ref "R19") (pin "1") (pinfunction "1_1") (pintype "passive"))
      (node (ref "R20") (pin "1") (pinfunction "1_1") (pintype "passive"))
      (node (ref "R21") (pin "1") (pinfunction "1_1") (pintype "passive"))
      (node (ref "R22") (pin "1") (pinfunction "1_1") (pintype "passive"))
      (node (ref "R24") (pin "2") (pinfunction "2_2") (pintype "passive"))
      (node (ref "R27") (pin "2") (pinfunction "2_2") (pintype "passive"))
      (node (ref "R28") (pin "2") (pinfunction "2_2") (pintype "passive"))
      (node (ref "R29") (pin "2") (pinfunction "2_2") (pintype "passive"))
      (node (ref "R30") (pin "1") (pinfunction "1_1") (pintype "passive"))
      (node (ref "R33") (pin "1") (pinfunction "1_1") (pintype "passive"))
      (node (ref "R35") (pin "1") (pinfunction "1_1") (pintype "passive"))
      (node (ref "R37") (pin "1") (pinfunction "1_1") (pintype "passive"))
      (node (ref "R4") (pin "1") (pinfunction "1_1") (pintype "passive"))
      (node (ref "R40") (pin "1") (pinfunction "1_1") (pintype "passive"))
      (node (ref "R44") (pin "1") (pinfunction "1_1") (pintype "passive"))
      (node (ref "R46") (pin "1") (pinfunction "1_1") (pintype "passive"))
      (node (ref "R48") (pin "1") (pinfunction "1_1") (pintype "passive"))
      (node (ref "R51") (pin "1") (pinfunction "1_1") (pintype "passive"))
      (node (ref "R54") (pin "1") (pinfunction "1_1") (pintype "passive"))
      (node (ref "R55") (pin "1") (pinfunction "1_1") (pintype "passive"))
      (node (ref "R58") (pin "1") (pinfunction "1_1") (pintype "passive"))
      (node (ref "R6") (pin "1") (pinfunction "1_1") (pintype "passive"))
      (node (ref "REG5") (pin "2") (pinfunction "GND_2") (pintype "power_in"))
      (node (ref "S5") (pin "B") (pinfunction "B_B") (pintype "passive"))
      (node (ref "S5") (pin "B1") (pinfunction "B1_B1") (pintype "passive"))
      (node (ref "U10") (pin "4") (pinfunction "V-_4") (pintype "power_in"))
      (node (ref "U2") (pin "11") (pinfunction "V-_11") (pintype "power_in"))
      (node (ref "U4") (pin "4") (pinfunction "V-_4") (pintype "power_in"))
      (node (ref "U4") (pin "5") (pinfunction "+IN_5") (pintype "input"))
      (node (ref "U9") (pin "15") (pinfunction "GND_15") (pintype "power_in"))
    )
    (net (code "6") (name "Net-(BATA-S)") (class "Default")
      (node (ref "BAT") (pin "1") (pinfunction "S_1") (pintype "passive"))
      (node (ref "CON_CHRG") (pin "3") (pinfunction "BAT_IN_3") (pintype "power_in"))
      (node (ref "F1") (pin "1") (pinfunction "1_1") (pintype "passive"))
    )
    (net (code "7") (name "Net-(C20-Pad1)") (class "Default")
      (node (ref "C20") (pin "1") (pinfunction "1_1") (pintype "passive"))
      (node (ref "R7") (pin "2") (pinfunction "2_2") (pintype "passive"))
      (node (ref "R8") (pin "1") (pinfunction "1_1") (pintype "passive"))
    )
    (net (code "8") (name "Net-(C21-Pad1)") (class "Default")
      (node (ref "C21") (pin "1") (pinfunction "1_1") (pintype "passive"))
      (node (ref "J4") (pin "2") (pinfunction "2_2") (pintype "passive"))
      (node (ref "J4") (pin "5") (pinfunction "5_5") (pintype "passive"))
      (node (ref "R7") (pin "1") (pinfunction "1_1") (pintype "passive"))
    )
    (net (code "9") (name "Net-(C22-Pad2)") (class "Default")
      (node (ref "C22") (pin "2") (pinfunction "2_2") (pintype "passive"))
      (node (ref "R13") (pin "2") (pinfunction "2_2") (pintype "passive"))
    )
    (net (code "10") (name "Net-(C23-Pad1)") (class "Default")
      (node (ref "C23") (pin "1") (pinfunction "1_1") (pintype "passive"))
      (node (ref "R14") (pin "2") (pinfunction "2_2") (pintype "passive"))
    )
    (net (code "11") (name "Net-(C24-Pad1)") (class "Default")
      (node (ref "C24") (pin "1") (pinfunction "1_1") (pintype "passive"))
      (node (ref "R15") (pin "2") (pinfunction "2_2") (pintype "passive"))
    )
    (net (code "12") (name "Net-(C43-Pad1)") (class "Default")
      (node (ref "C43") (pin "1") (pinfunction "1_1") (pintype "passive"))
      (node (ref "R11") (pin "1") (pinfunction "1_1") (pintype "passive"))
    )
    (net (code "13") (name "Net-(DAC-VOUT_A)") (class "Default")
      (node (ref "DAC") (pin "8") (pinfunction "VOUT_A_8") (pintype "output"))
      (node (ref "R42") (pin "1") (pinfunction "1_1") (pintype "passive"))
    )
    (net (code "14") (name "Net-(DAC-VOUT_B)") (class "Default")
      (node (ref "DAC") (pin "5") (pinfunction "VOUT_B_5") (pintype "output"))
      (node (ref "R31") (pin "1") (pinfunction "1_1") (pintype "passive"))
    )
    (net (code "15") (name "Net-(IC1-(ADC2)PA2)") (class "Default")
      (node (ref "D5") (pin "C") (pinfunction "C_C") (pintype "passive"))
      (node (ref "IC1") (pin "35") (pinfunction "(ADC2)PA2_35") (pintype "bidirectional"))
      (node (ref "R3") (pin "1") (pinfunction "1_1") (pintype "passive"))
      (node (ref "R4") (pin "2") (pinfunction "2_2") (pintype "passive"))
    )
    (net (code "16") (name "Net-(IC1-(ADC3)PA3)") (class "Default")
      (node (ref "IC1") (pin "34") (pinfunction "(ADC3)PA3_34") (pintype "bidirectional"))
      (node (ref "R5") (pin "1") (pinfunction "1_1") (pintype "passive"))
      (node (ref "R6") (pin "2") (pinfunction "2_2") (pintype "passive"))
    )
    (net (code "17") (name "Net-(IC1-XTAL1)") (class "Default")
      (node (ref "C15") (pin "1") (pinfunction "1_1") (pintype "passive"))
      (node (ref "IC1") (pin "8") (pinfunction "XTAL1_8") (pintype "bidirectional"))
      (node (ref "Y2") (pin "1") (pinfunction "1_1") (pintype "passive"))
    )
    (net (code "18") (name "Net-(IC1-XTAL2)") (class "Default")
      (node (ref "C16") (pin "1") (pinfunction "1_1") (pintype "passive"))
      (node (ref "IC1") (pin "7") (pinfunction "XTAL2_7") (pintype "bidirectional"))
      (node (ref "Y2") (pin "2") (pinfunction "2_2") (pintype "passive"))
    )
    (net (code "19") (name "Net-(J2-Pad2)") (class "Default")
      (node (ref "J2") (pin "2") (pinfunction "2_2") (pintype "passive"))
      (node (ref "R18") (pin "1") (pinfunction "1_1") (pintype "passive"))
      (node (ref "R19") (pin "2") (pinfunction "2_2") (pintype "passive"))
    )
    (net (code "20") (name "Net-(J2-Pad5)") (class "Default")
      (node (ref "J2") (pin "5") (pinfunction "5_5") (pintype "passive"))
      (node (ref "R62") (pin "1") (pinfunction "1_1") (pintype "passive"))
    )
    (net (code "21") (name "Net-(J5-Pad2)") (class "Default")
      (node (ref "J5") (pin "2") (pinfunction "2_2") (pintype "passive"))
      (node (ref "R15") (pin "1") (pinfunction "1_1") (pintype "passive"))
    )
    (net (code "22") (name "Net-(J5-Pad5)") (class "Default")
      (node (ref "J5") (pin "5") (pinfunction "5_5") (pintype "passive"))
      (node (ref "R14") (pin "1") (pinfunction "1_1") (pintype "passive"))
    )
    (net (code "23") (name "Net-(J6-Pad1)") (class "Default")
      (node (ref "J6") (pin "1") (pinfunction "1_1") (pintype "passive"))
      (node (ref "TR1") (pin "1") (pinfunction "1_1") (pintype "passive"))
    )
    (net (code "24") (name "Net-(J6-Pad5)") (class "Default")
      (node (ref "J6") (pin "5") (pinfunction "5_5") (pintype "passive"))
      (node (ref "TR1") (pin "3") (pinfunction "3_3") (pintype "passive"))
    )
    (net (code "25") (name "Net-(J7-Pad1)") (class "Default")
      (node (ref "J7") (pin "1") (pinfunction "1_1") (pintype "passive"))
      (node (ref "TR2") (pin "1") (pinfunction "1_1") (pintype "passive"))
    )
    (net (code "26") (name "Net-(J7-Pad5)") (class "Default")
      (node (ref "J7") (pin "5") (pinfunction "5_5") (pintype "passive"))
      (node (ref "TR2") (pin "3") (pinfunction "3_3") (pintype "passive"))
    )
    (net (code "27") (name "Net-(J9-Pad2)") (class "Default")
      (node (ref "J9") (pin "2") (pinfunction "2_2") (pintype "passive"))
      (node (ref "R58") (pin "2") (pinfunction "2_2") (pintype "passive"))
      (node (ref "R9") (pin "1") (pinfunction "1_1") (pintype "passive"))
    )
    (net (code "28") (name "Net-(Q1-D-Pad2)") (class "Default")
      (node (ref "Q1") (pin "2") (pinfunction "D_2") (pintype "passive"))
      (node (ref "Q1") (pin "4") (pinfunction "D_4") (pintype "passive"))
      (node (ref "TR1") (pin "4") (pinfunction "4_4") (pintype "passive"))
    )
    (net (code "29") (name "Net-(Q1-G)") (class "Default")
      (node (ref "Q1") (pin "1") (pinfunction "G_1") (pintype "passive"))
      (node (ref "R38") (pin "2") (pinfunction "2_2") (pintype "passive"))
    )
    (net (code "30") (name "Net-(Q2-D-Pad2)") (class "Default")
      (node (ref "Q2") (pin "2") (pinfunction "D_2") (pintype "passive"))
      (node (ref "Q2") (pin "4") (pinfunction "D_4") (pintype "passive"))
      (node (ref "TR1") (pin "6") (pinfunction "6_6") (pintype "passive"))
    )
    (net (code "31") (name "Net-(Q2-G)") (class "Default")
      (node (ref "Q2") (pin "1") (pinfunction "G_1") (pintype "passive"))
      (node (ref "R41") (pin "2") (pinfunction "2_2") (pintype "passive"))
    )
    (net (code "32") (name "Net-(Q3-D-Pad2)") (class "Default")
      (node (ref "Q3") (pin "2") (pinfunction "D_2") (pintype "passive"))
      (node (ref "Q3") (pin "4") (pinfunction "D_4") (pintype "passive"))
      (node (ref "TR1") (pin "5") (pinfunction "5_5") (pintype "passive"))
    )
    (net (code "33") (name "Net-(Q3-G)") (class "Default")
      (node (ref "C39") (pin "1") (pinfunction "1_1") (pintype "passive"))
      (node (ref "Q3") (pin "1") (pinfunction "G_1") (pintype "passive"))
      (node (ref "R39") (pin "2") (pinfunction "2_2") (pintype "passive"))
    )
    (net (code "34") (name "Net-(Q4-D-Pad2)") (class "Default")
      (node (ref "Q4") (pin "2") (pinfunction "D_2") (pintype "passive"))
      (node (ref "Q4") (pin "4") (pinfunction "D_4") (pintype "passive"))
      (node (ref "TR2") (pin "4") (pinfunction "4_4") (pintype "passive"))
    )
    (net (code "35") (name "Net-(Q4-G)") (class "Default")
      (node (ref "Q4") (pin "1") (pinfunction "G_1") (pintype "passive"))
      (node (ref "R49") (pin "2") (pinfunction "2_2") (pintype "passive"))
    )
    (net (code "36") (name "Net-(Q5-D-Pad2)") (class "Default")
      (node (ref "Q5") (pin "2") (pinfunction "D_2") (pintype "passive"))
      (node (ref "Q5") (pin "4") (pinfunction "D_4") (pintype "passive"))
      (node (ref "TR2") (pin "6") (pinfunction "6_6") (pintype "passive"))
    )
    (net (code "37") (name "Net-(Q5-G)") (class "Default")
      (node (ref "Q5") (pin "1") (pinfunction "G_1") (pintype "passive"))
      (node (ref "R52") (pin "2") (pinfunction "2_2") (pintype "passive"))
    )
    (net (code "38") (name "Net-(Q6-D-Pad2)") (class "Default")
      (node (ref "Q6") (pin "2") (pinfunction "D_2") (pintype "passive"))
      (node (ref "Q6") (pin "4") (pinfunction "D_4") (pintype "passive"))
      (node (ref "TR2") (pin "5") (pinfunction "5_5") (pintype "passive"))
    )
    (net (code "39") (name "Net-(Q6-G)") (class "Default")
      (node (ref "C40") (pin "1") (pinfunction "1_1") (pintype "passive"))
      (node (ref "Q6") (pin "1") (pinfunction "G_1") (pintype "passive"))
      (node (ref "R50") (pin "2") (pinfunction "2_2") (pintype "passive"))
    )
    (net (code "40") (name "Net-(R55-Pad2)") (class "Default")
      (node (ref "R55") (pin "2") (pinfunction "2_2") (pintype "passive"))
      (node (ref "TU") (pin "1") (pinfunction "1_1") (pintype "passive"))
    )
    (net (code "41") (name "Net-(S5-P)") (class "Default")
      (node (ref "D4") (pin "C") (pinfunction "C_C") (pintype "passive"))
      (node (ref "F1") (pin "2") (pinfunction "2_2") (pintype "passive"))
      (node (ref "S5") (pin "2") (pinfunction "P_2") (pintype "passive"))
      (node (ref "S5") (pin "3") (pinfunction "S_3") (pintype "passive"))
    )
    (net (code "42") (name "Net-(U2A-+IN)") (class "Default")
      (node (ref "C28") (pin "2") (pinfunction "2_2") (pintype "passive"))
      (node (ref "R21") (pin "2") (pinfunction "2_2") (pintype "passive"))
      (node (ref "R62") (pin "2") (pinfunction "2_2") (pintype "passive"))
      (node (ref "U2") (pin "3") (pinfunction "+IN_3") (pintype "input"))
    )
    (net (code "43") (name "Net-(U2A--IN)") (class "Default")
      (node (ref "R24") (pin "1") (pinfunction "1_1") (pintype "passive"))
      (node (ref "R25") (pin "1") (pinfunction "1_1") (pintype "passive"))
      (node (ref "U2") (pin "2") (pinfunction "-IN_2") (pintype "input"))
    )
    (net (code "44") (name "Net-(U2A-OUT)") (class "Default")
      (node (ref "D2") (pin "A") (pinfunction "A_A") (pintype "passive"))
      (node (ref "R25") (pin "2") (pinfunction "2_2") (pintype "passive"))
      (node (ref "U2") (pin "1") (pinfunction "OUT_1") (pintype "output"))
      (node (ref "U2") (pin "12") (pinfunction "+IN_12") (pintype "input"))
    )
    (net (code "45") (name "Net-(U2B-+IN)") (class "Default")
      (node (ref "C26") (pin "2") (pinfunction "2_2") (pintype "passive"))
      (node (ref "R20") (pin "2") (pinfunction "2_2") (pintype "passive"))
      (node (ref "U2") (pin "5") (pinfunction "+IN_5") (pintype "input"))
    )
    (net (code "46") (name "Net-(U2B--IN)") (class "Default")
      (node (ref "R22") (pin "2") (pinfunction "2_2") (pintype "passive"))
      (node (ref "R23") (pin "1") (pinfunction "1_1") (pintype "passive"))
      (node (ref "U2") (pin "6") (pinfunction "-IN_6") (pintype "input"))
    )
    (net (code "47") (name "Net-(U2B-OUT)") (class "Default")
      (node (ref "D3") (pin "A") (pinfunction "A_A") (pintype "passive"))
      (node (ref "R23") (pin "2") (pinfunction "2_2") (pintype "passive"))
      (node (ref "U2") (pin "10") (pinfunction "+IN_10") (pintype "input"))
      (node (ref "U2") (pin "7") (pinfunction "OUT_7") (pintype "output"))
    )
    (net (code "48") (name "Net-(U2C--IN)") (class "Default")
      (node (ref "R26") (pin "1") (pinfunction "1_1") (pintype "passive"))
      (node (ref "R27") (pin "1") (pinfunction "1_1") (pintype "passive"))
      (node (ref "U2") (pin "13") (pinfunction "-IN_13") (pintype "input"))
      (node (ref "U2") (pin "9") (pinfunction "-IN_9") (pintype "input"))
    )
    (net (code "49") (name "Net-(U4A-+IN)") (class "Default")
      (node (ref "C21") (pin "2") (pinfunction "2_2") (pintype "passive"))
      (node (ref "R10") (pin "2") (pinfunction "2_2") (pintype "passive"))
      (node (ref "R61") (pin "1") (pinfunction "1_1") (pintype "passive"))
      (node (ref "U4") (pin "3") (pinfunction "+IN_3") (pintype "input"))
    )
    (net (code "50") (name "Net-(U4A--IN)") (class "Default")
      (node (ref "R11") (pin "2") (pinfunction "2_2") (pintype "passive"))
      (node (ref "R12") (pin "1") (pinfunction "1_1") (pintype "passive"))
      (node (ref "U4") (pin "2") (pinfunction "-IN_2") (pintype "input"))
    )
    (net (code "51") (name "Net-(U4A-OUT)") (class "Default")
      (node (ref "R12") (pin "2") (pinfunction "2_2") (pintype "passive"))
      (node (ref "R13") (pin "1") (pinfunction "1_1") (pintype "passive"))
      (node (ref "U4") (pin "1") (pinfunction "OUT_1") (pintype "output"))
      (node (ref "U4") (pin "6") (pinfunction "-IN_6") (pintype "input"))
    )
    (net (code "52") (name "Net-(U9A-C1+)") (class "Default")
      (node (ref "C35") (pin "1") (pinfunction "1_1") (pintype "passive"))
      (node (ref "U9") (pin "1") (pinfunction "C1+_1") (pintype "bidirectional"))
    )
    (net (code "53") (name "Net-(U9A-C1-)") (class "Default")
      (node (ref "C35") (pin "2") (pinfunction "2_2") (pintype "passive"))
      (node (ref "U9") (pin "3") (pinfunction "C1-_3") (pintype "bidirectional"))
    )
    (net (code "54") (name "Net-(U9A-C2+)") (class "Default")
      (node (ref "C36") (pin "1") (pinfunction "1_1") (pintype "passive"))
      (node (ref "U9") (pin "4") (pinfunction "C2+_4") (pintype "bidirectional"))
    )
    (net (code "55") (name "Net-(U9A-C2-)") (class "Default")
      (node (ref "C36") (pin "2") (pinfunction "2_2") (pintype "passive"))
      (node (ref "U9") (pin "5") (pinfunction "C2-_5") (pintype "bidirectional"))
    )
    (net (code "56") (name "Net-(U9A-R1IN)") (class "Default")
      (node (ref "J3") (pin "2") (pinfunction "2_2") (pintype "passive"))
      (node (ref "U9") (pin "13") (pinfunction "R1IN_13") (pintype "input"))
    )
    (net (code "57") (name "Net-(U9A-R2IN)") (class "Default")
      (node (ref "J3") (pin "4") (pinfunction "4_4") (pintype "passive"))
      (node (ref "U9") (pin "8") (pinfunction "R2IN_8") (pintype "input"))
    )
    (net (code "58") (name "Net-(U9A-R2OUT)") (class "Default")
      (node (ref "R9") (pin "2") (pinfunction "2_2") (pintype "passive"))
      (node (ref "U9") (pin "9") (pinfunction "R2OUT_9") (pintype "output"))
    )
    (net (code "59") (name "Net-(U9A-T1OUT)") (class "Default")
      (node (ref "J3") (pin "5") (pinfunction "5_5") (pintype "passive"))
      (node (ref "U9") (pin "14") (pinfunction "T1OUT_14") (pintype "output"))
    )
    (net (code "60") (name "Net-(U9A-T2IN)") (class "Default")
      (node (ref "J9") (pin "3") (pinfunction "3_3") (pintype "passive"))
      (node (ref "U9") (pin "10") (pinfunction "T2IN_10") (pintype "input"))
    )
    (net (code "61") (name "Net-(U9A-T2OUT)") (class "Default")
      (node (ref "J3") (pin "3") (pinfunction "3_3") (pintype "passive"))
      (node (ref "U9") (pin "7") (pinfunction "T2OUT_7") (pintype "output"))
    )
    (net (code "62") (name "Net-(U9A-V+)") (class "Default")
      (node (ref "C33") (pin "2") (pinfunction "2_2") (pintype "passive"))
      (node (ref "U9") (pin "2") (pinfunction "V+_2") (pintype "bidirectional"))
    )
    (net (code "63") (name "Net-(U9A-V-)") (class "Default")
      (node (ref "C34") (pin "1") (pinfunction "1_1") (pintype "passive"))
      (node (ref "U9") (pin "6") (pinfunction "V-_6") (pintype "bidirectional"))
    )
    (net (code "64") (name "Net-(U10A-+IN)") (class "Default")
      (node (ref "R31") (pin "2") (pinfunction "2_2") (pintype "passive"))
      (node (ref "R32") (pin "1") (pinfunction "1_1") (pintype "passive"))
      (node (ref "R33") (pin "2") (pinfunction "2_2") (pintype "passive"))
      (node (ref "U10") (pin "3") (pinfunction "+IN_3") (pintype "input"))
    )
    (net (code "65") (name "Net-(U10A--IN)") (class "Default")
      (node (ref "R34") (pin "1") (pinfunction "1_1") (pintype "passive"))
      (node (ref "R35") (pin "2") (pinfunction "2_2") (pintype "passive"))
      (node (ref "R36") (pin "1") (pinfunction "1_1") (pintype "passive"))
      (node (ref "U10") (pin "2") (pinfunction "-IN_2") (pintype "input"))
    )
    (net (code "66") (name "Net-(U10A-OUT)") (class "Default")
      (node (ref "R36") (pin "2") (pinfunction "2_2") (pintype "passive"))
      (node (ref "R39") (pin "1") (pinfunction "1_1") (pintype "passive"))
      (node (ref "U10") (pin "1") (pinfunction "OUT_1") (pintype "output"))
    )
    (net (code "67") (name "Net-(U10B-+IN)") (class "Default")
      (node (ref "R42") (pin "2") (pinfunction "2_2") (pintype "passive"))
      (node (ref "R43") (pin "1") (pinfunction "1_1") (pintype "passive"))
      (node (ref "R44") (pin "2") (pinfunction "2_2") (pintype "passive"))
      (node (ref "U10") (pin "5") (pinfunction "+IN_5") (pintype "input"))
    )
    (net (code "68") (name "Net-(U10B--IN)") (class "Default")
      (node (ref "R45") (pin "1") (pinfunction "1_1") (pintype "passive"))
      (node (ref "R46") (pin "2") (pinfunction "2_2") (pintype "passive"))
      (node (ref "R47") (pin "1") (pinfunction "1_1") (pintype "passive"))
      (node (ref "U10") (pin "6") (pinfunction "-IN_6") (pintype "input"))
    )
    (net (code "69") (name "Net-(U10B-OUT)") (class "Default")
      (node (ref "R47") (pin "2") (pinfunction "2_2") (pintype "passive"))
      (node (ref "R50") (pin "1") (pinfunction "1_1") (pintype "passive"))
      (node (ref "U10") (pin "7") (pinfunction "OUT_7") (pintype "output"))
    )
    (net (code "70") (name "PA0") (class "Default")
      (node (ref "IC1") (pin "37") (pinfunction "(ADC0)PA0_37") (pintype "bidirectional"))
      (node (ref "Q1") (pin "3") (pinfunction "S_3") (pintype "passive"))
      (node (ref "Q2") (pin "3") (pinfunction "S_3") (pintype "passive"))
      (node (ref "Q4") (pin "3") (pinfunction "S_3") (pintype "passive"))
      (node (ref "Q5") (pin "3") (pinfunction "S_3") (pintype "passive"))
      (node (ref "R30") (pin "2") (pinfunction "2_2") (pintype "passive"))
      (node (ref "R54") (pin "2") (pinfunction "2_2") (pintype "passive"))
      (node (ref "TU") (pin "2") (pinfunction "2_2") (pintype "passive"))
    )
    (net (code "71") (name "PA1") (class "Default")
      (node (ref "C25") (pin "1") (pinfunction "1_1") (pintype "passive"))
      (node (ref "C26") (pin "1") (pinfunction "1_1") (pintype "passive"))
      (node (ref "IC1") (pin "36") (pinfunction "(ADC1)PA1_36") (pintype "bidirectional"))
      (node (ref "J11") (pin "5") (pinfunction "KL_5") (pintype "passive"))
    )
    (net (code "72") (name "PA4") (class "Default")
      (node (ref "IC1") (pin "33") (pinfunction "(ADC4)PA4_33") (pintype "bidirectional"))
      (node (ref "J11") (pin "9") (pinfunction "KL_9") (pintype "passive"))
    )
    (net (code "73") (name "PA5") (class "Default")
      (node (ref "IC1") (pin "32") (pinfunction "(ADC5)PA5_32") (pintype "bidirectional"))
      (node (ref "J11") (pin "11") (pinfunction "KL_11") (pintype "passive"))
    )
    (net (code "74") (name "PA6") (class "Default")
      (node (ref "C31") (pin "1") (pinfunction "1_1") (pintype "passive"))
      (node (ref "D2") (pin "C") (pinfunction "C_C") (pintype "passive"))
      (node (ref "IC1") (pin "31") (pinfunction "(ADC6)PA6_31") (pintype "bidirectional"))
      (node (ref "R29") (pin "1") (pinfunction "1_1") (pintype "passive"))
    )
    (net (code "75") (name "PA7") (class "Default")
      (node (ref "C30") (pin "1") (pinfunction "1_1") (pintype "passive"))
      (node (ref "D3") (pin "C") (pinfunction "C_C") (pintype "passive"))
      (node (ref "IC1") (pin "30") (pinfunction "(ADC7)PA7_30") (pintype "bidirectional"))
      (node (ref "R28") (pin "1") (pinfunction "1_1") (pintype "passive"))
    )
    (net (code "76") (name "PB0") (class "Default")
      (node (ref "IC1") (pin "40") (pinfunction "(T0/XCK)PB0_40") (pintype "bidirectional"))
      (node (ref "R48") (pin "2") (pinfunction "2_2") (pintype "passive"))
      (node (ref "R49") (pin "1") (pinfunction "1_1") (pintype "passive"))
    )
    (net (code "77") (name "PB1") (class "Default")
      (node (ref "IC1") (pin "41") (pinfunction "(T1)PB1_41") (pintype "bidirectional"))
      (node (ref "R51") (pin "2") (pinfunction "2_2") (pintype "passive"))
      (node (ref "R52") (pin "1") (pinfunction "1_1") (pintype "passive"))
    )
    (net (code "78") (name "PB2") (class "Default")
      (node (ref "IC1") (pin "42") (pinfunction "(AIN0/INT2)PB2_42") (pintype "bidirectional"))
      (node (ref "R37") (pin "2") (pinfunction "2_2") (pintype "passive"))
      (node (ref "R38") (pin "1") (pinfunction "1_1") (pintype "passive"))
    )
    (net (code "79") (name "PB3") (class "Default")
      (node (ref "IC1") (pin "43") (pinfunction "(AIN1/OC0)PB3_43") (pintype "bidirectional"))
      (node (ref "R40") (pin "2") (pinfunction "2_2") (pintype "passive"))
      (node (ref "R41") (pin "1") (pinfunction "1_1") (pintype "passive"))
    )
    (net (code "80") (name "PB5") (class "Default")
      (node (ref "DAC") (pin "3") (pinfunction "D_IN_3") (pintype "input"))
      (node (ref "IC1") (pin "1") (pinfunction "(MOSI)PB5_1") (pintype "bidirectional"))
      (node (ref "JP1") (pin "4") (pinfunction "S_4") (pintype "passive"))
    )
    (net (code "81") (name "PB6") (class "Default")
      (node (ref "IC1") (pin "2") (pinfunction "(MISO)PB6_2") (pintype "bidirectional"))
      (node (ref "JP1") (pin "1") (pinfunction "S_1") (pintype "passive"))
    )
    (net (code "82") (name "PB7") (class "Default")
      (node (ref "DAC") (pin "2") (pinfunction "SCK_2") (pintype "input"))
      (node (ref "IC1") (pin "3") (pinfunction "(SCK)PB7_3") (pintype "bidirectional"))
      (node (ref "JP1") (pin "3") (pinfunction "S_3") (pintype "passive"))
    )
    (net (code "83") (name "PC0") (class "Default")
      (node (ref "IC1") (pin "19") (pinfunction "PC0(SCL)_19") (pintype "bidirectional"))
      (node (ref "J11") (pin "2") (pinfunction "KL_2") (pintype "passive"))
    )
    (net (code "84") (name "PC1") (class "Default")
      (node (ref "IC1") (pin "20") (pinfunction "PC1(SDA)_20") (pintype "bidirectional"))
      (node (ref "J11") (pin "4") (pinfunction "KL_4") (pintype "passive"))
    )
    (net (code "85") (name "PC2") (class "Default")
      (node (ref "IC1") (pin "21") (pinfunction "(TCK)PC2_21") (pintype "bidirectional"))
      (node (ref "J11") (pin "6") (pinfunction "KL_6") (pintype "passive"))
    )
    (net (code "86") (name "PC3") (class "Default")
      (node (ref "IC1") (pin "22") (pinfunction "(TMS)PC3_22") (pintype "bidirectional"))
      (node (ref "J11") (pin "8") (pinfunction "KL_8") (pintype "passive"))
    )
    (net (code "87") (name "PC4") (class "Default")
      (node (ref "IC1") (pin "23") (pinfunction "(TDO)PC4_23") (pintype "bidirectional"))
      (node (ref "J11") (pin "10") (pinfunction "KL_10") (pintype "passive"))
    )
    (net (code "88") (name "PC5") (class "Default")
      (node (ref "IC1") (pin "24") (pinfunction "(TDI)PC5_24") (pintype "bidirectional"))
      (node (ref "J11") (pin "12") (pinfunction "KL_12") (pintype "passive"))
    )
    (net (code "89") (name "PC6") (class "Default")
      (node (ref "IC1") (pin "25") (pinfunction "(TOSC1)PC6_25") (pintype "bidirectional"))
      (node (ref "J11") (pin "14") (pinfunction "KL_14") (pintype "passive"))
    )
    (net (code "90") (name "PC7") (class "Default")
      (node (ref "IC1") (pin "26") (pinfunction "(TOSC2)PC7_26") (pintype "bidirectional"))
      (node (ref "J11") (pin "16") (pinfunction "KL_16") (pintype "passive"))
    )
    (net (code "91") (name "PD0") (class "Default")
      (node (ref "IC1") (pin "9") (pinfunction "(RXD)PD0_9") (pintype "bidirectional"))
      (node (ref "U9") (pin "12") (pinfunction "R1OUT_12") (pintype "output"))
    )
    (net (code "92") (name "PD1") (class "Default")
      (node (ref "IC1") (pin "10") (pinfunction "(TXD)PD1_10") (pintype "bidirectional"))
      (node (ref "U9") (pin "11") (pinfunction "T1IN_11") (pintype "input"))
    )
    (net (code "93") (name "PD2") (class "Default")
      (node (ref "IC1") (pin "11") (pinfunction "(INT0)PD2_11") (pintype "bidirectional"))
      (node (ref "U2") (pin "14") (pinfunction "OUT_14") (pintype "output"))
    )
    (net (code "94") (name "PD3") (class "Default")
      (node (ref "IC1") (pin "12") (pinfunction "(INT1)PD3_12") (pintype "bidirectional"))
      (node (ref "U2") (pin "8") (pinfunction "OUT_8") (pintype "output"))
    )
    (net (code "95") (name "PD5") (class "Default")
      (node (ref "IC1") (pin "14") (pinfunction "(OC1A)PD5_14") (pintype "bidirectional"))
      (node (ref "J11") (pin "15") (pinfunction "KL_15") (pintype "passive"))
    )
    (net (code "96") (name "PD6") (class "Default")
      (node (ref "IC1") (pin "15") (pinfunction "(ICP)PD6_15") (pintype "bidirectional"))
      (node (ref "J11") (pin "13") (pinfunction "KL_13") (pintype "passive"))
    )
    (net (code "97") (name "PD7") (class "Default")
      (node (ref "IC1") (pin "16") (pinfunction "(OC2)PD7_16") (pintype "bidirectional"))
      (node (ref "J11") (pin "18") (pinfunction "KL_18") (pintype "passive"))
    )
    (net (code "98") (name "RB4") (class "Default")
      (node (ref "C27") (pin "1") (pinfunction "1_1") (pintype "passive"))
      (node (ref "C28") (pin "1") (pinfunction "1_1") (pintype "passive"))
      (node (ref "J11") (pin "7") (pinfunction "KL_7") (pintype "passive"))
    )
    (net (code "99") (name "RB9") (class "Default")
      (node (ref "C22") (pin "1") (pinfunction "1_1") (pintype "passive"))
      (node (ref "C24") (pin "2") (pinfunction "2_2") (pintype "passive"))
      (node (ref "J11") (pin "3") (pinfunction "KL_3") (pintype "passive"))
      (node (ref "R17") (pin "1") (pinfunction "1_1") (pintype "passive"))
    )
    (net (code "100") (name "RB10") (class "Default")
      (node (ref "C23") (pin "2") (pinfunction "2_2") (pintype "passive"))
      (node (ref "J11") (pin "1") (pinfunction "KL_1") (pintype "passive"))
      (node (ref "R16") (pin "1") (pinfunction "1_1") (pintype "passive"))
    )
    (net (code "101") (name "RESET") (class "Default")
      (node (ref "C37") (pin "2") (pinfunction "2_2") (pintype "passive"))
      (node (ref "IC1") (pin "4") (pinfunction "RESET_4") (pintype "input"))
      (node (ref "JP1") (pin "5") (pinfunction "S_5") (pintype "passive"))
      (node (ref "R53") (pin "1") (pinfunction "1_1") (pintype "passive"))
    )
    (net (code "102") (name "STATE") (class "Default")
      (node (ref "J11") (pin "17") (pinfunction "KL_17") (pintype "passive"))
      (node (ref "J9") (pin "1") (pinfunction "1_1") (pintype "passive"))
    )
    (net (code "103") (name "V+") (class "Default")
      (node (ref "CON_CHRG") (pin "4") (pinfunction "V+_4") (pintype "power_in"))
      (node (ref "J8") (pin "PWR") (pinfunction "PWR_PWR") (pintype "bidirectional"))
      (node (ref "R3") (pin "2") (pinfunction "2_2") (pintype "passive"))
    )
    (net (code "104") (name "unconnected-(CON_CHRG-Pad2)") (class "Default")
      (node (ref "CON_CHRG") (pin "2") (pinfunction "2_2") (pintype "no_connect"))
    )
    (net (code "105") (name "unconnected-(CON_CHRG-Pad5)") (class "Default")
      (node (ref "CON_CHRG") (pin "5") (pinfunction "5_5") (pintype "no_connect"))
    )
    (net (code "106") (name "unconnected-(IC1-(SS)PB4-Pad44)") (class "Default")
      (node (ref "IC1") (pin "44") (pinfunction "(SS)PB4_44") (pintype "bidirectional"))
    )
    (net (code "107") (name "unconnected-(J2-Pad3)") (class "Default")
      (node (ref "J2") (pin "3") (pinfunction "3_3") (pintype "passive"))
    )
    (net (code "108") (name "unconnected-(J2-Pad4)") (class "Default")
      (node (ref "J2") (pin "4") (pinfunction "4_4") (pintype "passive"))
    )
    (net (code "109") (name "unconnected-(J4-Pad3)") (class "Default")
      (node (ref "J4") (pin "3") (pinfunction "3_3") (pintype "passive"))
    )
    (net (code "110") (name "unconnected-(J4-Pad4)") (class "Default")
      (node (ref "J4") (pin "4") (pinfunction "4_4") (pintype "passive"))
    )
    (net (code "111") (name "unconnected-(J5-Pad3)") (class "Default")
      (node (ref "J5") (pin "3") (pinfunction "3_3") (pintype "passive"))
    )
    (net (code "112") (name "unconnected-(J5-Pad4)") (class "Default")
      (node (ref "J5") (pin "4") (pinfunction "4_4") (pintype "passive"))
    )
    (net (code "113") (name "unconnected-(J6-Pad2)") (class "Default")
      (node (ref "J6") (pin "2") (pinfunction "2_2") (pintype "passive"))
    )
    (net (code "114") (name "unconnected-(J6-Pad3)") (class "Default")
      (node (ref "J6") (pin "3") (pinfunction "3_3") (pintype "passive"))
    )
    (net (code "115") (name "unconnected-(J6-Pad4)") (class "Default")
      (node (ref "J6") (pin "4") (pinfunction "4_4") (pintype "passive"))
    )
    (net (code "116") (name "unconnected-(J7-Pad2)") (class "Default")
      (node (ref "J7") (pin "2") (pinfunction "2_2") (pintype "passive"))
    )
    (net (code "117") (name "unconnected-(J7-Pad3)") (class "Default")
      (node (ref "J7") (pin "3") (pinfunction "3_3") (pintype "passive"))
    )
    (net (code "118") (name "unconnected-(J7-Pad4)") (class "Default")
      (node (ref "J7") (pin "4") (pinfunction "4_4") (pintype "passive"))
    )
    (net (code "119") (name "unconnected-(J9-Pad6)") (class "Default")
      (node (ref "J9") (pin "6") (pinfunction "6_6") (pintype "passive"))
    )
    (net (code "120") (name "unconnected-(TR1-Pad2)") (class "Default")
      (node (ref "TR1") (pin "2") (pinfunction "2_2") (pintype "passive"))
    )
    (net (code "121") (name "unconnected-(TR2-Pad2)") (class "Default")
      (node (ref "TR2") (pin "2") (pinfunction "2_2") (pintype "passive"))
    )
    (net (code "122") (name "unconnected-(U4B-OUT-Pad7)") (class "Default")
      (node (ref "U4") (pin "7") (pinfunction "OUT_7") (pintype "output"))
    )
    (net (code "123") (name "~{CS}") (class "Default")
      (node (ref "DAC") (pin "1") (pinfunction "CS/LD_1") (pintype "input"))
      (node (ref "IC1") (pin "13") (pinfunction "(OC1B)PD4_13") (pintype "bidirectional"))
    )
  )
)
